# 16encoder.net
KiCad netlist of a schematic drawn in Altium Designer
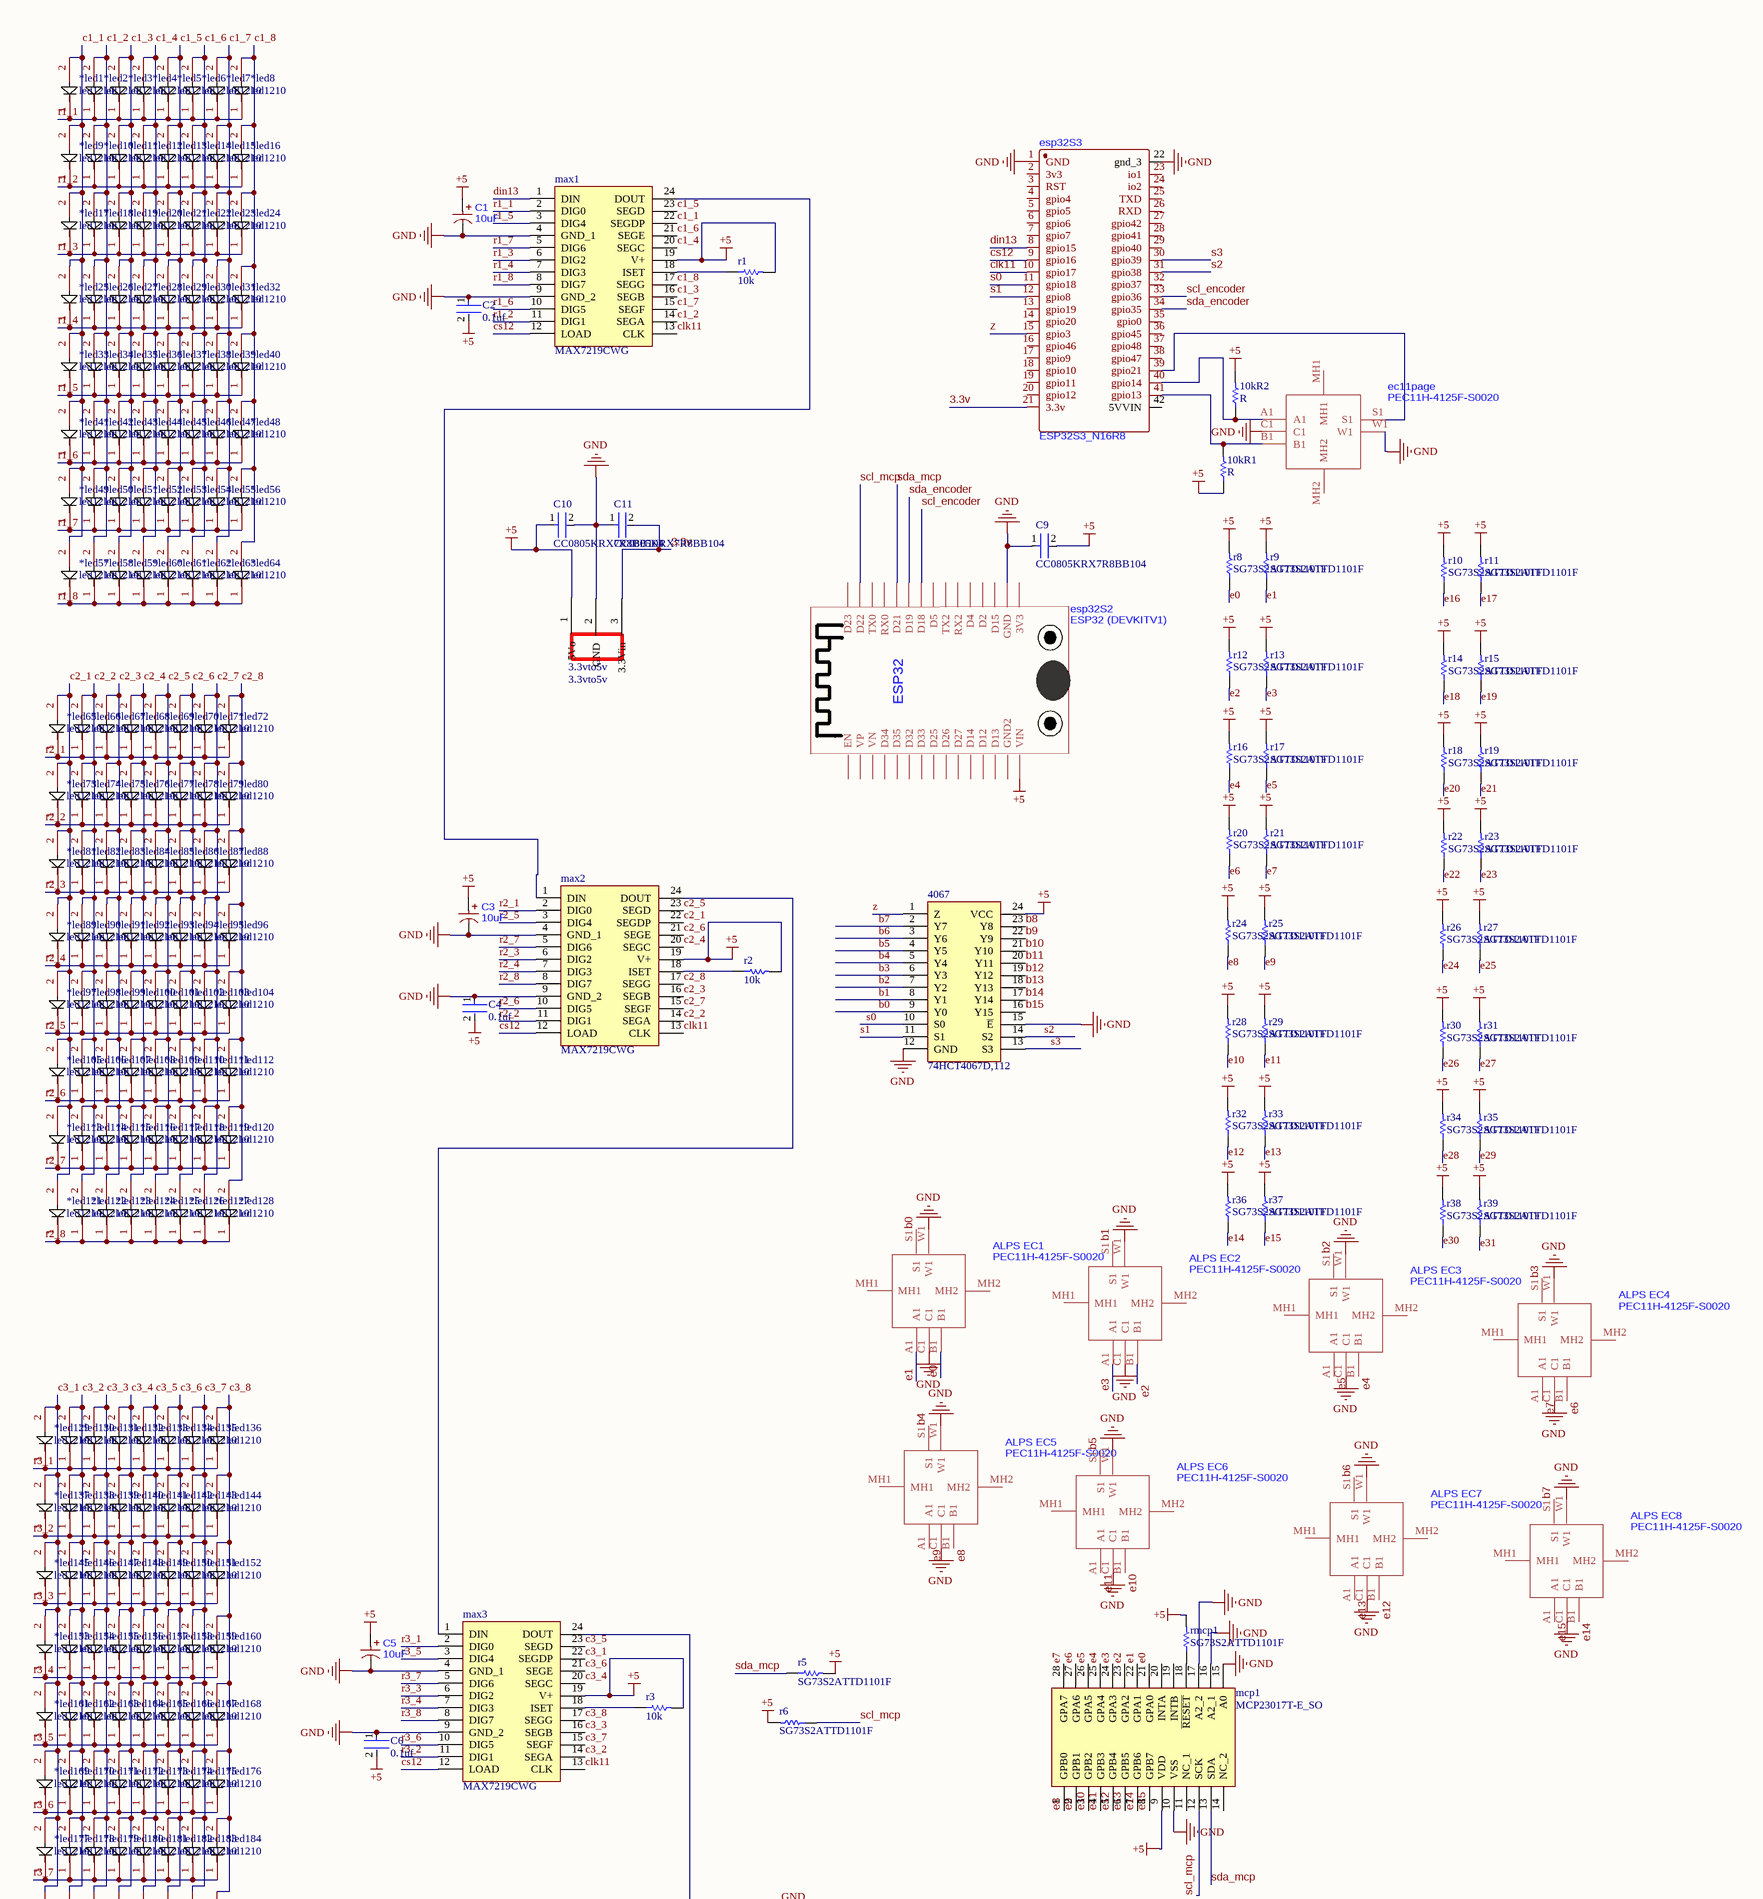
[diagram p0: 16encoder.SchDoc, top]
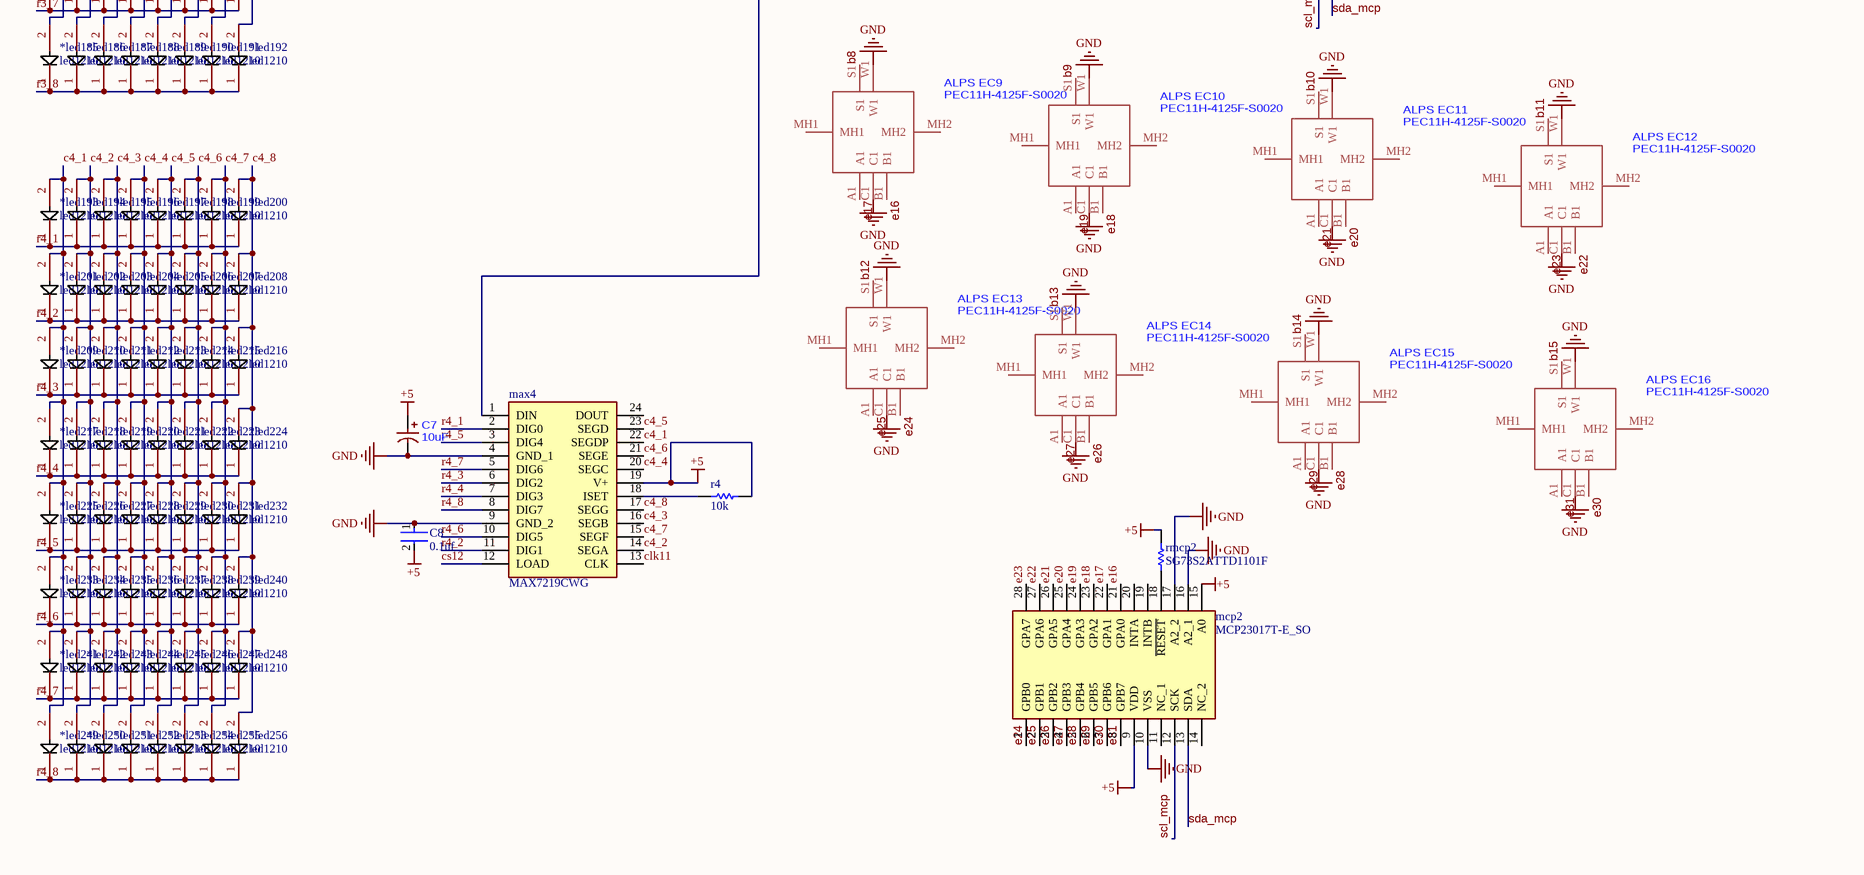
[diagram p1: 16encoder.SchDoc, bottom]

(export (version "E")
  (design (tool "Eeschema 10.0.6"))
  (components
    (comp (ref "*led1") (value "led1210") (footprint "1210贴片led") (libsource (lib "8") (part "led1210")))
    (comp (ref "*led2") (value "led1210") (footprint "1210贴片led") (libsource (lib "8") (part "led1210")))
    (comp (ref "*led3") (value "led1210") (footprint "1210贴片led") (libsource (lib "8") (part "led1210")))
    (comp (ref "*led4") (value "led1210") (footprint "1210贴片led") (libsource (lib "8") (part "led1210")))
    (comp (ref "*led5") (value "led1210") (footprint "1210贴片led") (libsource (lib "8") (part "led1210")))
    (comp (ref "*led6") (value "led1210") (footprint "1210贴片led") (libsource (lib "8") (part "led1210")))
    (comp (ref "*led7") (value "led1210") (footprint "1210贴片led") (libsource (lib "8") (part "led1210")))
    (comp (ref "*led8") (value "led1210") (footprint "1210贴片led") (libsource (lib "8") (part "led1210")))
    (comp (ref "*led9") (value "led1210") (footprint "1210贴片led") (libsource (lib "8") (part "led1210")))
    (comp (ref "*led10") (value "led1210") (footprint "1210贴片led") (libsource (lib "8") (part "led1210")))
    (comp (ref "*led11") (value "led1210") (footprint "1210贴片led") (libsource (lib "8") (part "led1210")))
    (comp (ref "*led12") (value "led1210") (footprint "1210贴片led") (libsource (lib "8") (part "led1210")))
    (comp (ref "*led13") (value "led1210") (footprint "1210贴片led") (libsource (lib "8") (part "led1210")))
    (comp (ref "*led14") (value "led1210") (footprint "1210贴片led") (libsource (lib "8") (part "led1210")))
    (comp (ref "*led15") (value "led1210") (footprint "1210贴片led") (libsource (lib "8") (part "led1210")))
    (comp (ref "*led16") (value "led1210") (footprint "1210贴片led") (libsource (lib "8") (part "led1210")))
    (comp (ref "*led17") (value "led1210") (footprint "1210贴片led") (libsource (lib "8") (part "led1210")))
    (comp (ref "*led18") (value "led1210") (footprint "1210贴片led") (libsource (lib "8") (part "led1210")))
    (comp (ref "*led19") (value "led1210") (footprint "1210贴片led") (libsource (lib "8") (part "led1210")))
    (comp (ref "*led20") (value "led1210") (footprint "1210贴片led") (libsource (lib "8") (part "led1210")))
    (comp (ref "*led21") (value "led1210") (footprint "1210贴片led") (libsource (lib "8") (part "led1210")))
    (comp (ref "*led22") (value "led1210") (footprint "1210贴片led") (libsource (lib "8") (part "led1210")))
    (comp (ref "*led23") (value "led1210") (footprint "1210贴片led") (libsource (lib "8") (part "led1210")))
    (comp (ref "*led24") (value "led1210") (footprint "1210贴片led") (libsource (lib "8") (part "led1210")))
    (comp (ref "*led25") (value "led1210") (footprint "1210贴片led") (libsource (lib "8") (part "led1210")))
    (comp (ref "*led26") (value "led1210") (footprint "1210贴片led") (libsource (lib "8") (part "led1210")))
    (comp (ref "*led27") (value "led1210") (footprint "1210贴片led") (libsource (lib "8") (part "led1210")))
    (comp (ref "*led28") (value "led1210") (footprint "1210贴片led") (libsource (lib "8") (part "led1210")))
    (comp (ref "*led29") (value "led1210") (footprint "1210贴片led") (libsource (lib "8") (part "led1210")))
    (comp (ref "*led30") (value "led1210") (footprint "1210贴片led") (libsource (lib "8") (part "led1210")))
    (comp (ref "*led31") (value "led1210") (footprint "1210贴片led") (libsource (lib "8") (part "led1210")))
    (comp (ref "*led32") (value "led1210") (footprint "1210贴片led") (libsource (lib "8") (part "led1210")))
    (comp (ref "*led33") (value "led1210") (footprint "1210贴片led") (libsource (lib "8") (part "led1210")))
    (comp (ref "*led34") (value "led1210") (footprint "1210贴片led") (libsource (lib "8") (part "led1210")))
    (comp (ref "*led35") (value "led1210") (footprint "1210贴片led") (libsource (lib "8") (part "led1210")))
    (comp (ref "*led36") (value "led1210") (footprint "1210贴片led") (libsource (lib "8") (part "led1210")))
    (comp (ref "*led37") (value "led1210") (footprint "1210贴片led") (libsource (lib "8") (part "led1210")))
    (comp (ref "*led38") (value "led1210") (footprint "1210贴片led") (libsource (lib "8") (part "led1210")))
    (comp (ref "*led39") (value "led1210") (footprint "1210贴片led") (libsource (lib "8") (part "led1210")))
    (comp (ref "*led40") (value "led1210") (footprint "1210贴片led") (libsource (lib "8") (part "led1210")))
    (comp (ref "*led41") (value "led1210") (footprint "1210贴片led") (libsource (lib "8") (part "led1210")))
    (comp (ref "*led42") (value "led1210") (footprint "1210贴片led") (libsource (lib "8") (part "led1210")))
    (comp (ref "*led43") (value "led1210") (footprint "1210贴片led") (libsource (lib "8") (part "led1210")))
    (comp (ref "*led44") (value "led1210") (footprint "1210贴片led") (libsource (lib "8") (part "led1210")))
    (comp (ref "*led45") (value "led1210") (footprint "1210贴片led") (libsource (lib "8") (part "led1210")))
    (comp (ref "*led46") (value "led1210") (footprint "1210贴片led") (libsource (lib "8") (part "led1210")))
    (comp (ref "*led47") (value "led1210") (footprint "1210贴片led") (libsource (lib "8") (part "led1210")))
    (comp (ref "*led48") (value "led1210") (footprint "1210贴片led") (libsource (lib "8") (part "led1210")))
    (comp (ref "*led49") (value "led1210") (footprint "1210贴片led") (libsource (lib "8") (part "led1210")))
    (comp (ref "*led50") (value "led1210") (footprint "1210贴片led") (libsource (lib "8") (part "led1210")))
    (comp (ref "*led51") (value "led1210") (footprint "1210贴片led") (libsource (lib "8") (part "led1210")))
    (comp (ref "*led52") (value "led1210") (footprint "1210贴片led") (libsource (lib "8") (part "led1210")))
    (comp (ref "*led53") (value "led1210") (footprint "1210贴片led") (libsource (lib "8") (part "led1210")))
    (comp (ref "*led54") (value "led1210") (footprint "1210贴片led") (libsource (lib "8") (part "led1210")))
    (comp (ref "*led55") (value "led1210") (footprint "1210贴片led") (libsource (lib "8") (part "led1210")))
    (comp (ref "*led56") (value "led1210") (footprint "1210贴片led") (libsource (lib "8") (part "led1210")))
    (comp (ref "*led57") (value "led1210") (footprint "1210贴片led") (libsource (lib "8") (part "led1210")))
    (comp (ref "*led58") (value "led1210") (footprint "1210贴片led") (libsource (lib "8") (part "led1210")))
    (comp (ref "*led59") (value "led1210") (footprint "1210贴片led") (libsource (lib "8") (part "led1210")))
    (comp (ref "*led60") (value "led1210") (footprint "1210贴片led") (libsource (lib "8") (part "led1210")))
    (comp (ref "*led61") (value "led1210") (footprint "1210贴片led") (libsource (lib "8") (part "led1210")))
    (comp (ref "*led62") (value "led1210") (footprint "1210贴片led") (libsource (lib "8") (part "led1210")))
    (comp (ref "*led63") (value "led1210") (footprint "1210贴片led") (libsource (lib "8") (part "led1210")))
    (comp (ref "*led64") (value "led1210") (footprint "1210贴片led") (libsource (lib "8") (part "led1210")))
    (comp (ref "*led65") (value "led1210") (footprint "1210贴片led") (libsource (lib "8") (part "led1210")))
    (comp (ref "*led66") (value "led1210") (footprint "1210贴片led") (libsource (lib "8") (part "led1210")))
    (comp (ref "*led67") (value "led1210") (footprint "1210贴片led") (libsource (lib "8") (part "led1210")))
    (comp (ref "*led68") (value "led1210") (footprint "1210贴片led") (libsource (lib "8") (part "led1210")))
    (comp (ref "*led69") (value "led1210") (footprint "1210贴片led") (libsource (lib "8") (part "led1210")))
    (comp (ref "*led70") (value "led1210") (footprint "1210贴片led") (libsource (lib "8") (part "led1210")))
    (comp (ref "*led71") (value "led1210") (footprint "1210贴片led") (libsource (lib "8") (part "led1210")))
    (comp (ref "*led72") (value "led1210") (footprint "1210贴片led") (libsource (lib "8") (part "led1210")))
    (comp (ref "*led73") (value "led1210") (footprint "1210贴片led") (libsource (lib "8") (part "led1210")))
    (comp (ref "*led74") (value "led1210") (footprint "1210贴片led") (libsource (lib "8") (part "led1210")))
    (comp (ref "*led75") (value "led1210") (footprint "1210贴片led") (libsource (lib "8") (part "led1210")))
    (comp (ref "*led76") (value "led1210") (footprint "1210贴片led") (libsource (lib "8") (part "led1210")))
    (comp (ref "*led77") (value "led1210") (footprint "1210贴片led") (libsource (lib "8") (part "led1210")))
    (comp (ref "*led78") (value "led1210") (footprint "1210贴片led") (libsource (lib "8") (part "led1210")))
    (comp (ref "*led79") (value "led1210") (footprint "1210贴片led") (libsource (lib "8") (part "led1210")))
    (comp (ref "*led80") (value "led1210") (footprint "1210贴片led") (libsource (lib "8") (part "led1210")))
    (comp (ref "*led81") (value "led1210") (footprint "1210贴片led") (libsource (lib "8") (part "led1210")))
    (comp (ref "*led82") (value "led1210") (footprint "1210贴片led") (libsource (lib "8") (part "led1210")))
    (comp (ref "*led83") (value "led1210") (footprint "1210贴片led") (libsource (lib "8") (part "led1210")))
    (comp (ref "*led84") (value "led1210") (footprint "1210贴片led") (libsource (lib "8") (part "led1210")))
    (comp (ref "*led85") (value "led1210") (footprint "1210贴片led") (libsource (lib "8") (part "led1210")))
    (comp (ref "*led86") (value "led1210") (footprint "1210贴片led") (libsource (lib "8") (part "led1210")))
    (comp (ref "*led87") (value "led1210") (footprint "1210贴片led") (libsource (lib "8") (part "led1210")))
    (comp (ref "*led88") (value "led1210") (footprint "1210贴片led") (libsource (lib "8") (part "led1210")))
    (comp (ref "*led89") (value "led1210") (footprint "1210贴片led") (libsource (lib "8") (part "led1210")))
    (comp (ref "*led90") (value "led1210") (footprint "1210贴片led") (libsource (lib "8") (part "led1210")))
    (comp (ref "*led91") (value "led1210") (footprint "1210贴片led") (libsource (lib "8") (part "led1210")))
    (comp (ref "*led92") (value "led1210") (footprint "1210贴片led") (libsource (lib "8") (part "led1210")))
    (comp (ref "*led93") (value "led1210") (footprint "1210贴片led") (libsource (lib "8") (part "led1210")))
    (comp (ref "*led94") (value "led1210") (footprint "1210贴片led") (libsource (lib "8") (part "led1210")))
    (comp (ref "*led95") (value "led1210") (footprint "1210贴片led") (libsource (lib "8") (part "led1210")))
    (comp (ref "*led96") (value "led1210") (footprint "1210贴片led") (libsource (lib "8") (part "led1210")))
    (comp (ref "*led97") (value "led1210") (footprint "1210贴片led") (libsource (lib "8") (part "led1210")))
    (comp (ref "*led98") (value "led1210") (footprint "1210贴片led") (libsource (lib "8") (part "led1210")))
    (comp (ref "*led99") (value "led1210") (footprint "1210贴片led") (libsource (lib "8") (part "led1210")))
    (comp (ref "*led100") (value "led1210") (footprint "1210贴片led") (libsource (lib "8") (part "led1210")))
    (comp (ref "*led101") (value "led1210") (footprint "1210贴片led") (libsource (lib "8") (part "led1210")))
    (comp (ref "*led102") (value "led1210") (footprint "1210贴片led") (libsource (lib "8") (part "led1210")))
    (comp (ref "*led103") (value "led1210") (footprint "1210贴片led") (libsource (lib "8") (part "led1210")))
    (comp (ref "*led104") (value "led1210") (footprint "1210贴片led") (libsource (lib "8") (part "led1210")))
    (comp (ref "*led105") (value "led1210") (footprint "1210贴片led") (libsource (lib "8") (part "led1210")))
    (comp (ref "*led106") (value "led1210") (footprint "1210贴片led") (libsource (lib "8") (part "led1210")))
    (comp (ref "*led107") (value "led1210") (footprint "1210贴片led") (libsource (lib "8") (part "led1210")))
    (comp (ref "*led108") (value "led1210") (footprint "1210贴片led") (libsource (lib "8") (part "led1210")))
    (comp (ref "*led109") (value "led1210") (footprint "1210贴片led") (libsource (lib "8") (part "led1210")))
    (comp (ref "*led110") (value "led1210") (footprint "1210贴片led") (libsource (lib "8") (part "led1210")))
    (comp (ref "*led111") (value "led1210") (footprint "1210贴片led") (libsource (lib "8") (part "led1210")))
    (comp (ref "*led112") (value "led1210") (footprint "1210贴片led") (libsource (lib "8") (part "led1210")))
    (comp (ref "*led113") (value "led1210") (footprint "1210贴片led") (libsource (lib "8") (part "led1210")))
    (comp (ref "*led114") (value "led1210") (footprint "1210贴片led") (libsource (lib "8") (part "led1210")))
    (comp (ref "*led115") (value "led1210") (footprint "1210贴片led") (libsource (lib "8") (part "led1210")))
    (comp (ref "*led116") (value "led1210") (footprint "1210贴片led") (libsource (lib "8") (part "led1210")))
    (comp (ref "*led117") (value "led1210") (footprint "1210贴片led") (libsource (lib "8") (part "led1210")))
    (comp (ref "*led118") (value "led1210") (footprint "1210贴片led") (libsource (lib "8") (part "led1210")))
    (comp (ref "*led119") (value "led1210") (footprint "1210贴片led") (libsource (lib "8") (part "led1210")))
    (comp (ref "*led120") (value "led1210") (footprint "1210贴片led") (libsource (lib "8") (part "led1210")))
    (comp (ref "*led121") (value "led1210") (footprint "1210贴片led") (libsource (lib "8") (part "led1210")))
    (comp (ref "*led122") (value "led1210") (footprint "1210贴片led") (libsource (lib "8") (part "led1210")))
    (comp (ref "*led123") (value "led1210") (footprint "1210贴片led") (libsource (lib "8") (part "led1210")))
    (comp (ref "*led124") (value "led1210") (footprint "1210贴片led") (libsource (lib "8") (part "led1210")))
    (comp (ref "*led125") (value "led1210") (footprint "1210贴片led") (libsource (lib "8") (part "led1210")))
    (comp (ref "*led126") (value "led1210") (footprint "1210贴片led") (libsource (lib "8") (part "led1210")))
    (comp (ref "*led127") (value "led1210") (footprint "1210贴片led") (libsource (lib "8") (part "led1210")))
    (comp (ref "*led128") (value "led1210") (footprint "1210贴片led") (libsource (lib "8") (part "led1210")))
    (comp (ref "*led129") (value "led1210") (footprint "1210贴片led") (libsource (lib "8") (part "led1210")))
    (comp (ref "*led130") (value "led1210") (footprint "1210贴片led") (libsource (lib "8") (part "led1210")))
    (comp (ref "*led131") (value "led1210") (footprint "1210贴片led") (libsource (lib "8") (part "led1210")))
    (comp (ref "*led132") (value "led1210") (footprint "1210贴片led") (libsource (lib "8") (part "led1210")))
    (comp (ref "*led133") (value "led1210") (footprint "1210贴片led") (libsource (lib "8") (part "led1210")))
    (comp (ref "*led134") (value "led1210") (footprint "1210贴片led") (libsource (lib "8") (part "led1210")))
    (comp (ref "*led135") (value "led1210") (footprint "1210贴片led") (libsource (lib "8") (part "led1210")))
    (comp (ref "*led136") (value "led1210") (footprint "1210贴片led") (libsource (lib "8") (part "led1210")))
    (comp (ref "*led137") (value "led1210") (footprint "1210贴片led") (libsource (lib "8") (part "led1210")))
    (comp (ref "*led138") (value "led1210") (footprint "1210贴片led") (libsource (lib "8") (part "led1210")))
    (comp (ref "*led139") (value "led1210") (footprint "1210贴片led") (libsource (lib "8") (part "led1210")))
    (comp (ref "*led140") (value "led1210") (footprint "1210贴片led") (libsource (lib "8") (part "led1210")))
    (comp (ref "*led141") (value "led1210") (footprint "1210贴片led") (libsource (lib "8") (part "led1210")))
    (comp (ref "*led142") (value "led1210") (footprint "1210贴片led") (libsource (lib "8") (part "led1210")))
    (comp (ref "*led143") (value "led1210") (footprint "1210贴片led") (libsource (lib "8") (part "led1210")))
    (comp (ref "*led144") (value "led1210") (footprint "1210贴片led") (libsource (lib "8") (part "led1210")))
    (comp (ref "*led145") (value "led1210") (footprint "1210贴片led") (libsource (lib "8") (part "led1210")))
    (comp (ref "*led146") (value "led1210") (footprint "1210贴片led") (libsource (lib "8") (part "led1210")))
    (comp (ref "*led147") (value "led1210") (footprint "1210贴片led") (libsource (lib "8") (part "led1210")))
    (comp (ref "*led148") (value "led1210") (footprint "1210贴片led") (libsource (lib "8") (part "led1210")))
    (comp (ref "*led149") (value "led1210") (footprint "1210贴片led") (libsource (lib "8") (part "led1210")))
    (comp (ref "*led150") (value "led1210") (footprint "1210贴片led") (libsource (lib "8") (part "led1210")))
    (comp (ref "*led151") (value "led1210") (footprint "1210贴片led") (libsource (lib "8") (part "led1210")))
    (comp (ref "*led152") (value "led1210") (footprint "1210贴片led") (libsource (lib "8") (part "led1210")))
    (comp (ref "*led153") (value "led1210") (footprint "1210贴片led") (libsource (lib "8") (part "led1210")))
    (comp (ref "*led154") (value "led1210") (footprint "1210贴片led") (libsource (lib "8") (part "led1210")))
    (comp (ref "*led155") (value "led1210") (footprint "1210贴片led") (libsource (lib "8") (part "led1210")))
    (comp (ref "*led156") (value "led1210") (footprint "1210贴片led") (libsource (lib "8") (part "led1210")))
    (comp (ref "*led157") (value "led1210") (footprint "1210贴片led") (libsource (lib "8") (part "led1210")))
    (comp (ref "*led158") (value "led1210") (footprint "1210贴片led") (libsource (lib "8") (part "led1210")))
    (comp (ref "*led159") (value "led1210") (footprint "1210贴片led") (libsource (lib "8") (part "led1210")))
    (comp (ref "*led160") (value "led1210") (footprint "1210贴片led") (libsource (lib "8") (part "led1210")))
    (comp (ref "*led161") (value "led1210") (footprint "1210贴片led") (libsource (lib "8") (part "led1210")))
    (comp (ref "*led162") (value "led1210") (footprint "1210贴片led") (libsource (lib "8") (part "led1210")))
    (comp (ref "*led163") (value "led1210") (footprint "1210贴片led") (libsource (lib "8") (part "led1210")))
    (comp (ref "*led164") (value "led1210") (footprint "1210贴片led") (libsource (lib "8") (part "led1210")))
    (comp (ref "*led165") (value "led1210") (footprint "1210贴片led") (libsource (lib "8") (part "led1210")))
    (comp (ref "*led166") (value "led1210") (footprint "1210贴片led") (libsource (lib "8") (part "led1210")))
    (comp (ref "*led167") (value "led1210") (footprint "1210贴片led") (libsource (lib "8") (part "led1210")))
    (comp (ref "*led168") (value "led1210") (footprint "1210贴片led") (libsource (lib "8") (part "led1210")))
    (comp (ref "*led169") (value "led1210") (footprint "1210贴片led") (libsource (lib "8") (part "led1210")))
    (comp (ref "*led170") (value "led1210") (footprint "1210贴片led") (libsource (lib "8") (part "led1210")))
    (comp (ref "*led171") (value "led1210") (footprint "1210贴片led") (libsource (lib "8") (part "led1210")))
    (comp (ref "*led172") (value "led1210") (footprint "1210贴片led") (libsource (lib "8") (part "led1210")))
    (comp (ref "*led173") (value "led1210") (footprint "1210贴片led") (libsource (lib "8") (part "led1210")))
    (comp (ref "*led174") (value "led1210") (footprint "1210贴片led") (libsource (lib "8") (part "led1210")))
    (comp (ref "*led175") (value "led1210") (footprint "1210贴片led") (libsource (lib "8") (part "led1210")))
    (comp (ref "*led176") (value "led1210") (footprint "1210贴片led") (libsource (lib "8") (part "led1210")))
    (comp (ref "*led177") (value "led1210") (footprint "1210贴片led") (libsource (lib "8") (part "led1210")))
    (comp (ref "*led178") (value "led1210") (footprint "1210贴片led") (libsource (lib "8") (part "led1210")))
    (comp (ref "*led179") (value "led1210") (footprint "1210贴片led") (libsource (lib "8") (part "led1210")))
    (comp (ref "*led180") (value "led1210") (footprint "1210贴片led") (libsource (lib "8") (part "led1210")))
    (comp (ref "*led181") (value "led1210") (footprint "1210贴片led") (libsource (lib "8") (part "led1210")))
    (comp (ref "*led182") (value "led1210") (footprint "1210贴片led") (libsource (lib "8") (part "led1210")))
    (comp (ref "*led183") (value "led1210") (footprint "1210贴片led") (libsource (lib "8") (part "led1210")))
    (comp (ref "*led184") (value "led1210") (footprint "1210贴片led") (libsource (lib "8") (part "led1210")))
    (comp (ref "*led185") (value "led1210") (footprint "1210贴片led") (libsource (lib "8") (part "led1210")))
    (comp (ref "*led186") (value "led1210") (footprint "1210贴片led") (libsource (lib "8") (part "led1210")))
    (comp (ref "*led187") (value "led1210") (footprint "1210贴片led") (libsource (lib "8") (part "led1210")))
    (comp (ref "*led188") (value "led1210") (footprint "1210贴片led") (libsource (lib "8") (part "led1210")))
    (comp (ref "*led189") (value "led1210") (footprint "1210贴片led") (libsource (lib "8") (part "led1210")))
    (comp (ref "*led190") (value "led1210") (footprint "1210贴片led") (libsource (lib "8") (part "led1210")))
    (comp (ref "*led191") (value "led1210") (footprint "1210贴片led") (libsource (lib "8") (part "led1210")))
    (comp (ref "*led192") (value "led1210") (footprint "1210贴片led") (libsource (lib "8") (part "led1210")))
    (comp (ref "*led193") (value "led1210") (footprint "1210贴片led") (libsource (lib "8") (part "led1210")))
    (comp (ref "*led194") (value "led1210") (footprint "1210贴片led") (libsource (lib "8") (part "led1210")))
    (comp (ref "*led195") (value "led1210") (footprint "1210贴片led") (libsource (lib "8") (part "led1210")))
    (comp (ref "*led196") (value "led1210") (footprint "1210贴片led") (libsource (lib "8") (part "led1210")))
    (comp (ref "*led197") (value "led1210") (footprint "1210贴片led") (libsource (lib "8") (part "led1210")))
    (comp (ref "*led198") (value "led1210") (footprint "1210贴片led") (libsource (lib "8") (part "led1210")))
    (comp (ref "*led199") (value "led1210") (footprint "1210贴片led") (libsource (lib "8") (part "led1210")))
    (comp (ref "*led200") (value "led1210") (footprint "1210贴片led") (libsource (lib "8") (part "led1210")))
    (comp (ref "*led201") (value "led1210") (footprint "1210贴片led") (libsource (lib "8") (part "led1210")))
    (comp (ref "*led202") (value "led1210") (footprint "1210贴片led") (libsource (lib "8") (part "led1210")))
    (comp (ref "*led203") (value "led1210") (footprint "1210贴片led") (libsource (lib "8") (part "led1210")))
    (comp (ref "*led204") (value "led1210") (footprint "1210贴片led") (libsource (lib "8") (part "led1210")))
    (comp (ref "*led205") (value "led1210") (footprint "1210贴片led") (libsource (lib "8") (part "led1210")))
    (comp (ref "*led206") (value "led1210") (footprint "1210贴片led") (libsource (lib "8") (part "led1210")))
    (comp (ref "*led207") (value "led1210") (footprint "1210贴片led") (libsource (lib "8") (part "led1210")))
    (comp (ref "*led208") (value "led1210") (footprint "1210贴片led") (libsource (lib "8") (part "led1210")))
    (comp (ref "*led209") (value "led1210") (footprint "1210贴片led") (libsource (lib "8") (part "led1210")))
    (comp (ref "*led210") (value "led1210") (footprint "1210贴片led") (libsource (lib "8") (part "led1210")))
    (comp (ref "*led211") (value "led1210") (footprint "1210贴片led") (libsource (lib "8") (part "led1210")))
    (comp (ref "*led212") (value "led1210") (footprint "1210贴片led") (libsource (lib "8") (part "led1210")))
    (comp (ref "*led213") (value "led1210") (footprint "1210贴片led") (libsource (lib "8") (part "led1210")))
    (comp (ref "*led214") (value "led1210") (footprint "1210贴片led") (libsource (lib "8") (part "led1210")))
    (comp (ref "*led215") (value "led1210") (footprint "1210贴片led") (libsource (lib "8") (part "led1210")))
    (comp (ref "*led216") (value "led1210") (footprint "1210贴片led") (libsource (lib "8") (part "led1210")))
    (comp (ref "*led217") (value "led1210") (footprint "1210贴片led") (libsource (lib "8") (part "led1210")))
    (comp (ref "*led218") (value "led1210") (footprint "1210贴片led") (libsource (lib "8") (part "led1210")))
    (comp (ref "*led219") (value "led1210") (footprint "1210贴片led") (libsource (lib "8") (part "led1210")))
    (comp (ref "*led220") (value "led1210") (footprint "1210贴片led") (libsource (lib "8") (part "led1210")))
    (comp (ref "*led221") (value "led1210") (footprint "1210贴片led") (libsource (lib "8") (part "led1210")))
    (comp (ref "*led222") (value "led1210") (footprint "1210贴片led") (libsource (lib "8") (part "led1210")))
    (comp (ref "*led223") (value "led1210") (footprint "1210贴片led") (libsource (lib "8") (part "led1210")))
    (comp (ref "*led224") (value "led1210") (footprint "1210贴片led") (libsource (lib "8") (part "led1210")))
    (comp (ref "*led225") (value "led1210") (footprint "1210贴片led") (libsource (lib "8") (part "led1210")))
    (comp (ref "*led226") (value "led1210") (footprint "1210贴片led") (libsource (lib "8") (part "led1210")))
    (comp (ref "*led227") (value "led1210") (footprint "1210贴片led") (libsource (lib "8") (part "led1210")))
    (comp (ref "*led228") (value "led1210") (footprint "1210贴片led") (libsource (lib "8") (part "led1210")))
    (comp (ref "*led229") (value "led1210") (footprint "1210贴片led") (libsource (lib "8") (part "led1210")))
    (comp (ref "*led230") (value "led1210") (footprint "1210贴片led") (libsource (lib "8") (part "led1210")))
    (comp (ref "*led231") (value "led1210") (footprint "1210贴片led") (libsource (lib "8") (part "led1210")))
    (comp (ref "*led232") (value "led1210") (footprint "1210贴片led") (libsource (lib "8") (part "led1210")))
    (comp (ref "*led233") (value "led1210") (footprint "1210贴片led") (libsource (lib "8") (part "led1210")))
    (comp (ref "*led234") (value "led1210") (footprint "1210贴片led") (libsource (lib "8") (part "led1210")))
    (comp (ref "*led235") (value "led1210") (footprint "1210贴片led") (libsource (lib "8") (part "led1210")))
    (comp (ref "*led236") (value "led1210") (footprint "1210贴片led") (libsource (lib "8") (part "led1210")))
    (comp (ref "*led237") (value "led1210") (footprint "1210贴片led") (libsource (lib "8") (part "led1210")))
    (comp (ref "*led238") (value "led1210") (footprint "1210贴片led") (libsource (lib "8") (part "led1210")))
    (comp (ref "*led239") (value "led1210") (footprint "1210贴片led") (libsource (lib "8") (part "led1210")))
    (comp (ref "*led240") (value "led1210") (footprint "1210贴片led") (libsource (lib "8") (part "led1210")))
    (comp (ref "*led241") (value "led1210") (footprint "1210贴片led") (libsource (lib "8") (part "led1210")))
    (comp (ref "*led242") (value "led1210") (footprint "1210贴片led") (libsource (lib "8") (part "led1210")))
    (comp (ref "*led243") (value "led1210") (footprint "1210贴片led") (libsource (lib "8") (part "led1210")))
    (comp (ref "*led244") (value "led1210") (footprint "1210贴片led") (libsource (lib "8") (part "led1210")))
    (comp (ref "*led245") (value "led1210") (footprint "1210贴片led") (libsource (lib "8") (part "led1210")))
    (comp (ref "*led246") (value "led1210") (footprint "1210贴片led") (libsource (lib "8") (part "led1210")))
    (comp (ref "*led247") (value "led1210") (footprint "1210贴片led") (libsource (lib "8") (part "led1210")))
    (comp (ref "*led248") (value "led1210") (footprint "1210贴片led") (libsource (lib "8") (part "led1210")))
    (comp (ref "*led249") (value "led1210") (footprint "1210贴片led") (libsource (lib "8") (part "led1210")))
    (comp (ref "*led250") (value "led1210") (footprint "1210贴片led") (libsource (lib "8") (part "led1210")))
    (comp (ref "*led251") (value "led1210") (footprint "1210贴片led") (libsource (lib "8") (part "led1210")))
    (comp (ref "*led252") (value "led1210") (footprint "1210贴片led") (libsource (lib "8") (part "led1210")))
    (comp (ref "*led253") (value "led1210") (footprint "1210贴片led") (libsource (lib "8") (part "led1210")))
    (comp (ref "*led254") (value "led1210") (footprint "1210贴片led") (libsource (lib "8") (part "led1210")))
    (comp (ref "*led255") (value "led1210") (footprint "1210贴片led") (libsource (lib "8") (part "led1210")))
    (comp (ref "*led256") (value "led1210") (footprint "1210贴片led") (libsource (lib "8") (part "led1210")))
    (comp (ref "3.3vto5v")
      (value "3.3vto5v")
      (footprint "3.3vto5v")
      (libsource (lib "8_1") (part "3.3vto5v"))
    )
    (comp (ref "10kR1")
      (value "R")
      (footprint "RESC2013X60X30LL20T20")
      (fields (field (name "MANUFACTURER") "KOA Speer") (field (name "PART NUMBER") "SG73S2ATTD1101F"))
      (libsource (lib "8_1") (part "CMP-2001-02660-1"))
    )
    (comp (ref "10kR2")
      (value "R")
      (footprint "RESC2013X60X30LL20T20")
      (fields (field (name "MANUFACTURER") "KOA Speer") (field (name "PART NUMBER") "SG73S2ATTD1101F"))
      (libsource (lib "8_1") (part "CMP-2001-02660-1"))
    )
    (comp (ref "4067")
      (value "74HCT4067D,112")
      (footprint "SamacSys:SOIC127P1032X265-24N")
      (description "Integrated Circuit")
      (fields (field (name "MOUSER PART NUMBER") "771-74HCT4067D"))
      (libsource (lib "*") (part "74HCT4067D,112"))
    )
    (comp (ref "ALPS EC1")
      (value "PEC11H-4125F-S0020")
      (footprint "ALPS EC11")
      (libsource (lib "midi_sub") (part "PEC11H-4125F-S0020"))
    )
    (comp (ref "ALPS EC2")
      (value "PEC11H-4125F-S0020")
      (footprint "ALPS EC11")
      (libsource (lib "midi_sub") (part "PEC11H-4125F-S0020"))
    )
    (comp (ref "ALPS EC3")
      (value "PEC11H-4125F-S0020")
      (footprint "ALPS EC11")
      (libsource (lib "midi_sub") (part "PEC11H-4125F-S0020"))
    )
    (comp (ref "ALPS EC4")
      (value "PEC11H-4125F-S0020")
      (footprint "ALPS EC11")
      (libsource (lib "midi_sub") (part "PEC11H-4125F-S0020"))
    )
    (comp (ref "ALPS EC5")
      (value "PEC11H-4125F-S0020")
      (footprint "ALPS EC11")
      (libsource (lib "midi_sub") (part "PEC11H-4125F-S0020"))
    )
    (comp (ref "ALPS EC6")
      (value "PEC11H-4125F-S0020")
      (footprint "ALPS EC11")
      (libsource (lib "midi_sub") (part "PEC11H-4125F-S0020"))
    )
    (comp (ref "ALPS EC7")
      (value "PEC11H-4125F-S0020")
      (footprint "ALPS EC11")
      (libsource (lib "midi_sub") (part "PEC11H-4125F-S0020"))
    )
    (comp (ref "ALPS EC8")
      (value "PEC11H-4125F-S0020")
      (footprint "ALPS EC11")
      (libsource (lib "midi_sub") (part "PEC11H-4125F-S0020"))
    )
    (comp (ref "ALPS EC9")
      (value "PEC11H-4125F-S0020")
      (footprint "ALPS EC11")
      (libsource (lib "midi_sub") (part "PEC11H-4125F-S0020"))
    )
    (comp (ref "ALPS EC10")
      (value "PEC11H-4125F-S0020")
      (footprint "ALPS EC11")
      (libsource (lib "midi_sub") (part "PEC11H-4125F-S0020"))
    )
    (comp (ref "ALPS EC11")
      (value "PEC11H-4125F-S0020")
      (footprint "ALPS EC11")
      (libsource (lib "midi_sub") (part "PEC11H-4125F-S0020"))
    )
    (comp (ref "ALPS EC12")
      (value "PEC11H-4125F-S0020")
      (footprint "ALPS EC11")
      (libsource (lib "midi_sub") (part "PEC11H-4125F-S0020"))
    )
    (comp (ref "ALPS EC13")
      (value "PEC11H-4125F-S0020")
      (footprint "ALPS EC11")
      (libsource (lib "midi_sub") (part "PEC11H-4125F-S0020"))
    )
    (comp (ref "ALPS EC14")
      (value "PEC11H-4125F-S0020")
      (footprint "ALPS EC11")
      (libsource (lib "midi_sub") (part "PEC11H-4125F-S0020"))
    )
    (comp (ref "ALPS EC15")
      (value "PEC11H-4125F-S0020")
      (footprint "ALPS EC11")
      (libsource (lib "midi_sub") (part "PEC11H-4125F-S0020"))
    )
    (comp (ref "ALPS EC16")
      (value "PEC11H-4125F-S0020")
      (footprint "ALPS EC11")
      (libsource (lib "midi_sub") (part "PEC11H-4125F-S0020"))
    )
    (comp (ref "C1")
      (value "10uF")
      (footprint "ELECTROLYTIC CAPACITOR SMD 4X5.4")
      (libsource (lib "sub_1") (part "4.3 X 4.3 ELECTROLYTIC  CAPACITOR SMD μF"))
    )
    (comp (ref "C2")
      (value "0.1uf")
      (footprint "FP-CC0805-0_85-IPC_A")
      (description "CAP CER 0.1UF 25V X7R 0805")
      (fields (field (name "MANUFACTURER PART NUMBER") "CC0805KRX7R8BB104") (field (name "TOLERANCE") "0.1"))
      (libsource (lib "sub_1") (part "CMP-1036-04410-2"))
    )
    (comp (ref "C3")
      (value "10uF")
      (footprint "ELECTROLYTIC CAPACITOR SMD 4X5.4")
      (libsource (lib "sub_1") (part "4.3 X 4.3 ELECTROLYTIC  CAPACITOR SMD μF"))
    )
    (comp (ref "C4")
      (value "0.1uf")
      (footprint "FP-CC0805-0_85-IPC_A")
      (description "CAP CER 0.1UF 25V X7R 0805")
      (fields (field (name "MANUFACTURER PART NUMBER") "CC0805KRX7R8BB104") (field (name "TOLERANCE") "0.1"))
      (libsource (lib "sub_1") (part "CMP-1036-04410-2"))
    )
    (comp (ref "C5")
      (value "10uF")
      (footprint "ELECTROLYTIC CAPACITOR SMD 4X5.4")
      (libsource (lib "sub_1") (part "4.3 X 4.3 ELECTROLYTIC  CAPACITOR SMD μF"))
    )
    (comp (ref "C6")
      (value "0.1uf")
      (footprint "FP-CC0805-0_85-IPC_A")
      (description "CAP CER 0.1UF 25V X7R 0805")
      (fields (field (name "MANUFACTURER PART NUMBER") "CC0805KRX7R8BB104") (field (name "TOLERANCE") "0.1"))
      (libsource (lib "sub_1") (part "CMP-1036-04410-2"))
    )
    (comp (ref "C7")
      (value "10uF")
      (footprint "ELECTROLYTIC CAPACITOR SMD 4X5.4")
      (libsource (lib "sub_1") (part "4.3 X 4.3 ELECTROLYTIC  CAPACITOR SMD μF"))
    )
    (comp (ref "C8")
      (value "0.1uf")
      (footprint "FP-CC0805-0_85-IPC_A")
      (description "CAP CER 0.1UF 25V X7R 0805")
      (fields (field (name "MANUFACTURER PART NUMBER") "CC0805KRX7R8BB104") (field (name "TOLERANCE") "0.1"))
      (libsource (lib "sub_1") (part "CMP-1036-04410-2"))
    )
    (comp (ref "C9")
      (value "CC0805KRX7R8BB104")
      (footprint "FP-CC0805-0_85-IPC_A")
      (description "CAP CER 0.1UF 25V X7R 0805")
      (fields (field (name "TOLERANCE") "0.1") (field (name "MANUFACTURER") "Yageo"))
      (libsource (lib "midi_sub") (part "CMP-1036-04410-2"))
    )
    (comp (ref "C10")
      (value "CC0805KRX7R8BB104")
      (footprint "FP-CC0805-0_85-IPC_A")
      (description "CAP CER 0.1UF 25V X7R 0805")
      (fields (field (name "TOLERANCE") "0.1") (field (name "MANUFACTURER") "Yageo"))
      (libsource (lib "midi_sub") (part "CMP-1036-04410-2"))
    )
    (comp (ref "C11")
      (value "CC0805KRX7R8BB104")
      (footprint "FP-CC0805-0_85-IPC_A")
      (description "CAP CER 0.1UF 25V X7R 0805")
      (fields (field (name "TOLERANCE") "0.1") (field (name "MANUFACTURER") "Yageo"))
      (libsource (lib "midi_sub") (part "CMP-1036-04410-2"))
    )
    (comp (ref "ec11page")
      (value "PEC11H-4125F-S0020")
      (footprint "ALPS EC11")
      (libsource (lib "midi_sub") (part "PEC11H-4125F-S0020"))
    )
    (comp (ref "esp32S2")
      (value "ESP32 (DEVKITV1)")
      (footprint "ESP32-DEVKITV1_ESP32-DEVKITV1")
      (libsource (lib "8_1") (part "ESP32 (DEVKITV1)"))
    )
    (comp (ref "esp32S3")
      (value "ESP32S3_N16R8")
      (footprint "ESP32 S3 N16R8")
      (libsource (lib "8_1") (part "ESP32S3_N16R8"))
    )
    (comp (ref "max1")
      (value "MAX7219CWG")
      (footprint "SamacSys:SOIC127P1032X265-24N")
      (description "Integrated Circuit")
      (fields (field (name "MOUSER PART NUMBER") "700-MAX7219CWG-NR"))
      (libsource (lib "*") (part "MAX7219CWG"))
    )
    (comp (ref "max2")
      (value "MAX7219CWG")
      (footprint "SamacSys:SOIC127P1032X265-24N")
      (description "Integrated Circuit")
      (fields (field (name "MOUSER PART NUMBER") "700-MAX7219CWG-NR"))
      (libsource (lib "*") (part "MAX7219CWG"))
    )
    (comp (ref "max3")
      (value "MAX7219CWG")
      (footprint "SamacSys:SOIC127P1032X265-24N")
      (description "Integrated Circuit")
      (fields (field (name "MOUSER PART NUMBER") "700-MAX7219CWG-NR"))
      (libsource (lib "*") (part "MAX7219CWG"))
    )
    (comp (ref "max4")
      (value "MAX7219CWG")
      (footprint "SamacSys:SOIC127P1032X265-24N")
      (description "Integrated Circuit")
      (fields (field (name "MOUSER PART NUMBER") "700-MAX7219CWG-NR"))
      (libsource (lib "*") (part "MAX7219CWG"))
    )
    (comp (ref "mcp1")
      (value "MCP23017T-E_SO")
      (footprint "SOIC127P1030X265-28N")
      (description "Integrated Circuit")
      (fields
        (field (name "MANUFACTURER_PART_NUMBER") "MCP23017T-E/SO")
        (field (name "MOUSER PART NUMBER") "579-MCP23017T-E/SO")
      )
      (libsource (lib "sub_1") (part "MCP23017T-E_SO"))
    )
    (comp (ref "mcp2")
      (value "MCP23017T-E_SO")
      (footprint "SOIC127P1030X265-28N")
      (description "Integrated Circuit")
      (fields
        (field (name "MANUFACTURER_PART_NUMBER") "MCP23017T-E/SO")
        (field (name "MOUSER PART NUMBER") "579-MCP23017T-E/SO")
      )
      (libsource (lib "sub_1") (part "MCP23017T-E_SO"))
    )
    (comp (ref "r1")
      (value "10k")
      (footprint "RESC2013X60X30LL20T20")
      (fields (field (name "MANUFACTURER") "KOA Speer") (field (name "PART NUMBER") "SG73S2ATTD1101F"))
      (libsource (lib "sub_1") (part "CMP-2001-02660-1"))
    )
    (comp (ref "r2")
      (value "10k")
      (footprint "RESC2013X60X30LL20T20")
      (fields (field (name "MANUFACTURER") "KOA Speer") (field (name "PART NUMBER") "SG73S2ATTD1101F"))
      (libsource (lib "sub_1") (part "CMP-2001-02660-1"))
    )
    (comp (ref "r3")
      (value "10k")
      (footprint "RESC2013X60X30LL20T20")
      (fields (field (name "MANUFACTURER") "KOA Speer") (field (name "PART NUMBER") "SG73S2ATTD1101F"))
      (libsource (lib "sub_1") (part "CMP-2001-02660-1"))
    )
    (comp (ref "r4")
      (value "10k")
      (footprint "RESC2013X60X30LL20T20")
      (fields (field (name "MANUFACTURER") "KOA Speer") (field (name "PART NUMBER") "SG73S2ATTD1101F"))
      (libsource (lib "sub_1") (part "CMP-2001-02660-1"))
    )
    (comp (ref "r5")
      (value "SG73S2ATTD1101F")
      (footprint "RESC2013X60X30LL20T20")
      (fields (field (name "MANUFACTURER") "KOA Speer"))
      (libsource (lib "sub_1") (part "CMP-2001-02660-1"))
    )
    (comp (ref "r6")
      (value "SG73S2ATTD1101F")
      (footprint "RESC2013X60X30LL20T20")
      (fields (field (name "MANUFACTURER") "KOA Speer"))
      (libsource (lib "sub_1") (part "CMP-2001-02660-1"))
    )
    (comp (ref "r8")
      (value "SG73S2ATTD1101F")
      (footprint "RESC2013X60X30LL20T20")
      (fields (field (name "MANUFACTURER") "KOA Speer"))
      (libsource (lib "sub_1") (part "CMP-2001-02660-1"))
    )
    (comp (ref "r9")
      (value "SG73S2ATTD1101F")
      (footprint "RESC2013X60X30LL20T20")
      (fields (field (name "MANUFACTURER") "KOA Speer"))
      (libsource (lib "sub_1") (part "CMP-2001-02660-1"))
    )
    (comp (ref "r10")
      (value "SG73S2ATTD1101F")
      (footprint "RESC2013X60X30LL20T20")
      (fields (field (name "MANUFACTURER") "KOA Speer"))
      (libsource (lib "sub_1") (part "CMP-2001-02660-1"))
    )
    (comp (ref "r11")
      (value "SG73S2ATTD1101F")
      (footprint "RESC2013X60X30LL20T20")
      (fields (field (name "MANUFACTURER") "KOA Speer"))
      (libsource (lib "sub_1") (part "CMP-2001-02660-1"))
    )
    (comp (ref "r12")
      (value "SG73S2ATTD1101F")
      (footprint "RESC2013X60X30LL20T20")
      (fields (field (name "MANUFACTURER") "KOA Speer"))
      (libsource (lib "sub_1") (part "CMP-2001-02660-1"))
    )
    (comp (ref "r13")
      (value "SG73S2ATTD1101F")
      (footprint "RESC2013X60X30LL20T20")
      (fields (field (name "MANUFACTURER") "KOA Speer"))
      (libsource (lib "sub_1") (part "CMP-2001-02660-1"))
    )
    (comp (ref "r14")
      (value "SG73S2ATTD1101F")
      (footprint "RESC2013X60X30LL20T20")
      (fields (field (name "MANUFACTURER") "KOA Speer"))
      (libsource (lib "sub_1") (part "CMP-2001-02660-1"))
    )
    (comp (ref "r15")
      (value "SG73S2ATTD1101F")
      (footprint "RESC2013X60X30LL20T20")
      (fields (field (name "MANUFACTURER") "KOA Speer"))
      (libsource (lib "sub_1") (part "CMP-2001-02660-1"))
    )
    (comp (ref "r16")
      (value "SG73S2ATTD1101F")
      (footprint "RESC2013X60X30LL20T20")
      (fields (field (name "MANUFACTURER") "KOA Speer"))
      (libsource (lib "sub_1") (part "CMP-2001-02660-1"))
    )
    (comp (ref "r17")
      (value "SG73S2ATTD1101F")
      (footprint "RESC2013X60X30LL20T20")
      (fields (field (name "MANUFACTURER") "KOA Speer"))
      (libsource (lib "sub_1") (part "CMP-2001-02660-1"))
    )
    (comp (ref "r18")
      (value "SG73S2ATTD1101F")
      (footprint "RESC2013X60X30LL20T20")
      (fields (field (name "MANUFACTURER") "KOA Speer"))
      (libsource (lib "sub_1") (part "CMP-2001-02660-1"))
    )
    (comp (ref "r19")
      (value "SG73S2ATTD1101F")
      (footprint "RESC2013X60X30LL20T20")
      (fields (field (name "MANUFACTURER") "KOA Speer"))
      (libsource (lib "sub_1") (part "CMP-2001-02660-1"))
    )
    (comp (ref "r20")
      (value "SG73S2ATTD1101F")
      (footprint "RESC2013X60X30LL20T20")
      (fields (field (name "MANUFACTURER") "KOA Speer"))
      (libsource (lib "sub_1") (part "CMP-2001-02660-1"))
    )
    (comp (ref "r21")
      (value "SG73S2ATTD1101F")
      (footprint "RESC2013X60X30LL20T20")
      (fields (field (name "MANUFACTURER") "KOA Speer"))
      (libsource (lib "sub_1") (part "CMP-2001-02660-1"))
    )
    (comp (ref "r22")
      (value "SG73S2ATTD1101F")
      (footprint "RESC2013X60X30LL20T20")
      (fields (field (name "MANUFACTURER") "KOA Speer"))
      (libsource (lib "sub_1") (part "CMP-2001-02660-1"))
    )
    (comp (ref "r23")
      (value "SG73S2ATTD1101F")
      (footprint "RESC2013X60X30LL20T20")
      (fields (field (name "MANUFACTURER") "KOA Speer"))
      (libsource (lib "sub_1") (part "CMP-2001-02660-1"))
    )
    (comp (ref "r24")
      (value "SG73S2ATTD1101F")
      (footprint "RESC2013X60X30LL20T20")
      (fields (field (name "MANUFACTURER") "KOA Speer"))
      (libsource (lib "sub_1") (part "CMP-2001-02660-1"))
    )
    (comp (ref "r25")
      (value "SG73S2ATTD1101F")
      (footprint "RESC2013X60X30LL20T20")
      (fields (field (name "MANUFACTURER") "KOA Speer"))
      (libsource (lib "sub_1") (part "CMP-2001-02660-1"))
    )
    (comp (ref "r26")
      (value "SG73S2ATTD1101F")
      (footprint "RESC2013X60X30LL20T20")
      (fields (field (name "MANUFACTURER") "KOA Speer"))
      (libsource (lib "sub_1") (part "CMP-2001-02660-1"))
    )
    (comp (ref "r27")
      (value "SG73S2ATTD1101F")
      (footprint "RESC2013X60X30LL20T20")
      (fields (field (name "MANUFACTURER") "KOA Speer"))
      (libsource (lib "sub_1") (part "CMP-2001-02660-1"))
    )
    (comp (ref "r28")
      (value "SG73S2ATTD1101F")
      (footprint "RESC2013X60X30LL20T20")
      (fields (field (name "MANUFACTURER") "KOA Speer"))
      (libsource (lib "sub_1") (part "CMP-2001-02660-1"))
    )
    (comp (ref "r29")
      (value "SG73S2ATTD1101F")
      (footprint "RESC2013X60X30LL20T20")
      (fields (field (name "MANUFACTURER") "KOA Speer"))
      (libsource (lib "sub_1") (part "CMP-2001-02660-1"))
    )
    (comp (ref "r30")
      (value "SG73S2ATTD1101F")
      (footprint "RESC2013X60X30LL20T20")
      (fields (field (name "MANUFACTURER") "KOA Speer"))
      (libsource (lib "sub_1") (part "CMP-2001-02660-1"))
    )
    (comp (ref "r31")
      (value "SG73S2ATTD1101F")
      (footprint "RESC2013X60X30LL20T20")
      (fields (field (name "MANUFACTURER") "KOA Speer"))
      (libsource (lib "sub_1") (part "CMP-2001-02660-1"))
    )
    (comp (ref "r32")
      (value "SG73S2ATTD1101F")
      (footprint "RESC2013X60X30LL20T20")
      (fields (field (name "MANUFACTURER") "KOA Speer"))
      (libsource (lib "sub_1") (part "CMP-2001-02660-1"))
    )
    (comp (ref "r33")
      (value "SG73S2ATTD1101F")
      (footprint "RESC2013X60X30LL20T20")
      (fields (field (name "MANUFACTURER") "KOA Speer"))
      (libsource (lib "sub_1") (part "CMP-2001-02660-1"))
    )
    (comp (ref "r34")
      (value "SG73S2ATTD1101F")
      (footprint "RESC2013X60X30LL20T20")
      (fields (field (name "MANUFACTURER") "KOA Speer"))
      (libsource (lib "sub_1") (part "CMP-2001-02660-1"))
    )
    (comp (ref "r35")
      (value "SG73S2ATTD1101F")
      (footprint "RESC2013X60X30LL20T20")
      (fields (field (name "MANUFACTURER") "KOA Speer"))
      (libsource (lib "sub_1") (part "CMP-2001-02660-1"))
    )
    (comp (ref "r36")
      (value "SG73S2ATTD1101F")
      (footprint "RESC2013X60X30LL20T20")
      (fields (field (name "MANUFACTURER") "KOA Speer"))
      (libsource (lib "sub_1") (part "CMP-2001-02660-1"))
    )
    (comp (ref "r37")
      (value "SG73S2ATTD1101F")
      (footprint "RESC2013X60X30LL20T20")
      (fields (field (name "MANUFACTURER") "KOA Speer"))
      (libsource (lib "sub_1") (part "CMP-2001-02660-1"))
    )
    (comp (ref "r38")
      (value "SG73S2ATTD1101F")
      (footprint "RESC2013X60X30LL20T20")
      (fields (field (name "MANUFACTURER") "KOA Speer"))
      (libsource (lib "sub_1") (part "CMP-2001-02660-1"))
    )
    (comp (ref "r39")
      (value "SG73S2ATTD1101F")
      (footprint "RESC2013X60X30LL20T20")
      (fields (field (name "MANUFACTURER") "KOA Speer"))
      (libsource (lib "sub_1") (part "CMP-2001-02660-1"))
    )
    (comp (ref "rmcp1")
      (value "SG73S2ATTD1101F")
      (footprint "RESC2013X60X30LL20T20")
      (fields (field (name "MANUFACTURER") "KOA Speer"))
      (libsource (lib "midi_sub") (part "CMP-2001-02660-1"))
    )
    (comp (ref "rmcp2")
      (value "SG73S2ATTD1101F")
      (footprint "RESC2013X60X30LL20T20")
      (fields (field (name "MANUFACTURER") "KOA Speer"))
      (libsource (lib "midi_sub") (part "CMP-2001-02660-1"))
    )
  )
  (nets
    (net (code "1") (name "+5") (class "Default")
      (node (ref "10kR1") (pin "1") (pinfunction "1_1") (pintype "passive"))
      (node (ref "10kR2") (pin "2") (pinfunction "2_2") (pintype "passive"))
      (node (ref "3.3vto5v") (pin "1") (pinfunction "5Vo_1") (pintype "passive"))
      (node (ref "4067") (pin "24") (pinfunction "VCC_24") (pintype "passive"))
      (node (ref "C1") (pin "1") (pinfunction "1_1") (pintype "passive"))
      (node (ref "C10") (pin "1") (pinfunction "1_1") (pintype "passive"))
      (node (ref "C2") (pin "2") (pinfunction "2_2") (pintype "passive"))
      (node (ref "C3") (pin "1") (pinfunction "1_1") (pintype "passive"))
      (node (ref "C4") (pin "2") (pinfunction "2_2") (pintype "passive"))
      (node (ref "C5") (pin "1") (pinfunction "1_1") (pintype "passive"))
      (node (ref "C6") (pin "2") (pinfunction "2_2") (pintype "passive"))
      (node (ref "C7") (pin "1") (pinfunction "1_1") (pintype "passive"))
      (node (ref "C8") (pin "2") (pinfunction "2_2") (pintype "passive"))
      (node (ref "C9") (pin "2") (pinfunction "2_2") (pintype "passive"))
      (node (ref "esp32S2") (pin "VIN") (pinfunction "VIN_VIN") (pintype "passive"))
      (node (ref "max1") (pin "19") (pinfunction "V+_19") (pintype "passive"))
      (node (ref "max2") (pin "19") (pinfunction "V+_19") (pintype "passive"))
      (node (ref "max3") (pin "19") (pinfunction "V+_19") (pintype "passive"))
      (node (ref "max4") (pin "19") (pinfunction "V+_19") (pintype "passive"))
      (node (ref "mcp1") (pin "9") (pinfunction "VDD_9") (pintype "passive"))
      (node (ref "mcp2") (pin "15") (pinfunction "A0_15") (pintype "passive"))
      (node (ref "mcp2") (pin "9") (pinfunction "VDD_9") (pintype "passive"))
      (node (ref "r1") (pin "2") (pinfunction "2_2") (pintype "passive"))
      (node (ref "r10") (pin "2") (pinfunction "2_2") (pintype "passive"))
      (node (ref "r11") (pin "2") (pinfunction "2_2") (pintype "passive"))
      (node (ref "r12") (pin "2") (pinfunction "2_2") (pintype "passive"))
      (node (ref "r13") (pin "2") (pinfunction "2_2") (pintype "passive"))
      (node (ref "r14") (pin "2") (pinfunction "2_2") (pintype "passive"))
      (node (ref "r15") (pin "2") (pinfunction "2_2") (pintype "passive"))
      (node (ref "r16") (pin "2") (pinfunction "2_2") (pintype "passive"))
      (node (ref "r17") (pin "2") (pinfunction "2_2") (pintype "passive"))
      (node (ref "r18") (pin "2") (pinfunction "2_2") (pintype "passive"))
      (node (ref "r19") (pin "2") (pinfunction "2_2") (pintype "passive"))
      (node (ref "r2") (pin "2") (pinfunction "2_2") (pintype "passive"))
      (node (ref "r20") (pin "2") (pinfunction "2_2") (pintype "passive"))
      (node (ref "r21") (pin "2") (pinfunction "2_2") (pintype "passive"))
      (node (ref "r22") (pin "2") (pinfunction "2_2") (pintype "passive"))
      (node (ref "r23") (pin "2") (pinfunction "2_2") (pintype "passive"))
      (node (ref "r24") (pin "2") (pinfunction "2_2") (pintype "passive"))
      (node (ref "r25") (pin "2") (pinfunction "2_2") (pintype "passive"))
      (node (ref "r26") (pin "2") (pinfunction "2_2") (pintype "passive"))
      (node (ref "r27") (pin "2") (pinfunction "2_2") (pintype "passive"))
      (node (ref "r28") (pin "2") (pinfunction "2_2") (pintype "passive"))
      (node (ref "r29") (pin "2") (pinfunction "2_2") (pintype "passive"))
      (node (ref "r3") (pin "2") (pinfunction "2_2") (pintype "passive"))
      (node (ref "r30") (pin "2") (pinfunction "2_2") (pintype "passive"))
      (node (ref "r31") (pin "2") (pinfunction "2_2") (pintype "passive"))
      (node (ref "r32") (pin "2") (pinfunction "2_2") (pintype "passive"))
      (node (ref "r33") (pin "2") (pinfunction "2_2") (pintype "passive"))
      (node (ref "r34") (pin "2") (pinfunction "2_2") (pintype "passive"))
      (node (ref "r35") (pin "2") (pinfunction "2_2") (pintype "passive"))
      (node (ref "r36") (pin "2") (pinfunction "2_2") (pintype "passive"))
      (node (ref "r37") (pin "2") (pinfunction "2_2") (pintype "passive"))
      (node (ref "r38") (pin "2") (pinfunction "2_2") (pintype "passive"))
      (node (ref "r39") (pin "2") (pinfunction "2_2") (pintype "passive"))
      (node (ref "r4") (pin "2") (pinfunction "2_2") (pintype "passive"))
      (node (ref "r5") (pin "2") (pinfunction "2_2") (pintype "passive"))
      (node (ref "r6") (pin "2") (pinfunction "2_2") (pintype "passive"))
      (node (ref "r8") (pin "2") (pinfunction "2_2") (pintype "passive"))
      (node (ref "r9") (pin "2") (pinfunction "2_2") (pintype "passive"))
      (node (ref "rmcp1") (pin "2") (pinfunction "2_2") (pintype "passive"))
      (node (ref "rmcp2") (pin "2") (pinfunction "2_2") (pintype "passive"))
    )
    (net (code "2") (name "/3.3v") (class "Default")
      (node (ref "3.3vto5v") (pin "3") (pinfunction "3.3Vin_3") (pintype "passive"))
      (node (ref "C11") (pin "2") (pinfunction "2_2") (pintype "passive"))
      (node (ref "esp32S3") (pin "21") (pinfunction "3.3v_21") (pintype "passive"))
    )
    (net (code "3") (name "/b0") (class "Default")
      (node (ref "4067") (pin "9") (pinfunction "Y0_9") (pintype "passive"))
      (node (ref "ALPS EC1") (pin "S1") (pinfunction "S1_S1") (pintype "passive"))
    )
    (net (code "4") (name "/b1") (class "Default")
      (node (ref "4067") (pin "8") (pinfunction "Y1_8") (pintype "passive"))
      (node (ref "ALPS EC2") (pin "S1") (pinfunction "S1_S1") (pintype "passive"))
    )
    (net (code "5") (name "/b2") (class "Default")
      (node (ref "4067") (pin "7") (pinfunction "Y2_7") (pintype "passive"))
      (node (ref "ALPS EC3") (pin "S1") (pinfunction "S1_S1") (pintype "passive"))
    )
    (net (code "6") (name "/b3") (class "Default")
      (node (ref "4067") (pin "6") (pinfunction "Y3_6") (pintype "passive"))
      (node (ref "ALPS EC4") (pin "S1") (pinfunction "S1_S1") (pintype "passive"))
    )
    (net (code "7") (name "/b4") (class "Default")
      (node (ref "4067") (pin "5") (pinfunction "Y4_5") (pintype "passive"))
      (node (ref "ALPS EC5") (pin "S1") (pinfunction "S1_S1") (pintype "passive"))
    )
    (net (code "8") (name "/b5") (class "Default")
      (node (ref "4067") (pin "4") (pinfunction "Y5_4") (pintype "passive"))
      (node (ref "ALPS EC6") (pin "S1") (pinfunction "S1_S1") (pintype "passive"))
    )
    (net (code "9") (name "/b6") (class "Default")
      (node (ref "4067") (pin "3") (pinfunction "Y6_3") (pintype "passive"))
      (node (ref "ALPS EC7") (pin "S1") (pinfunction "S1_S1") (pintype "passive"))
    )
    (net (code "10") (name "/b7") (class "Default")
      (node (ref "4067") (pin "2") (pinfunction "Y7_2") (pintype "passive"))
      (node (ref "ALPS EC8") (pin "S1") (pinfunction "S1_S1") (pintype "passive"))
    )
    (net (code "11") (name "/b8") (class "Default")
      (node (ref "4067") (pin "23") (pinfunction "Y8_23") (pintype "passive"))
      (node (ref "ALPS EC9") (pin "S1") (pinfunction "S1_S1") (pintype "passive"))
    )
    (net (code "12") (name "/b9") (class "Default")
      (node (ref "4067") (pin "22") (pinfunction "Y9_22") (pintype "passive"))
      (node (ref "ALPS EC10") (pin "S1") (pinfunction "S1_S1") (pintype "passive"))
    )
    (net (code "13") (name "/b10") (class "Default")
      (node (ref "4067") (pin "21") (pinfunction "Y10_21") (pintype "passive"))
      (node (ref "ALPS EC11") (pin "S1") (pinfunction "S1_S1") (pintype "passive"))
    )
    (net (code "14") (name "/b11") (class "Default")
      (node (ref "4067") (pin "20") (pinfunction "Y11_20") (pintype "passive"))
      (node (ref "ALPS EC12") (pin "S1") (pinfunction "S1_S1") (pintype "passive"))
    )
    (net (code "15") (name "/b12") (class "Default")
      (node (ref "4067") (pin "19") (pinfunction "Y12_19") (pintype "passive"))
      (node (ref "ALPS EC13") (pin "S1") (pinfunction "S1_S1") (pintype "passive"))
    )
    (net (code "16") (name "/b13") (class "Default")
      (node (ref "4067") (pin "18") (pinfunction "Y13_18") (pintype "passive"))
      (node (ref "ALPS EC14") (pin "S1") (pinfunction "S1_S1") (pintype "passive"))
    )
    (net (code "17") (name "/b14") (class "Default")
      (node (ref "4067") (pin "17") (pinfunction "Y14_17") (pintype "passive"))
      (node (ref "ALPS EC15") (pin "S1") (pinfunction "S1_S1") (pintype "passive"))
    )
    (net (code "18") (name "/b15") (class "Default")
      (node (ref "4067") (pin "16") (pinfunction "Y15_16") (pintype "passive"))
      (node (ref "ALPS EC16") (pin "S1") (pinfunction "S1_S1") (pintype "passive"))
    )
    (net (code "19") (name "/c1_1") (class "Default")
      (node (ref "*led1") (pin "2") (pinfunction "2_2") (pintype "passive"))
      (node (ref "*led17") (pin "2") (pinfunction "2_2") (pintype "passive"))
      (node (ref "*led25") (pin "2") (pinfunction "2_2") (pintype "passive"))
      (node (ref "*led33") (pin "2") (pinfunction "2_2") (pintype "passive"))
      (node (ref "*led41") (pin "2") (pinfunction "2_2") (pintype "passive"))
      (node (ref "*led49") (pin "2") (pinfunction "2_2") (pintype "passive"))
      (node (ref "*led57") (pin "2") (pinfunction "2_2") (pintype "passive"))
      (node (ref "*led9") (pin "2") (pinfunction "2_2") (pintype "passive"))
      (node (ref "max1") (pin "22") (pinfunction "SEGDP_22") (pintype "passive"))
    )
    (net (code "20") (name "/c1_2") (class "Default")
      (node (ref "*led10") (pin "2") (pinfunction "2_2") (pintype "passive"))
      (node (ref "*led18") (pin "2") (pinfunction "2_2") (pintype "passive"))
      (node (ref "*led2") (pin "2") (pinfunction "2_2") (pintype "passive"))
      (node (ref "*led26") (pin "2") (pinfunction "2_2") (pintype "passive"))
      (node (ref "*led34") (pin "2") (pinfunction "2_2") (pintype "passive"))
      (node (ref "*led42") (pin "2") (pinfunction "2_2") (pintype "passive"))
      (node (ref "*led50") (pin "2") (pinfunction "2_2") (pintype "passive"))
      (node (ref "*led58") (pin "2") (pinfunction "2_2") (pintype "passive"))
      (node (ref "max1") (pin "14") (pinfunction "SEGA_14") (pintype "passive"))
    )
    (net (code "21") (name "/c1_3") (class "Default")
      (node (ref "*led11") (pin "2") (pinfunction "2_2") (pintype "passive"))
      (node (ref "*led19") (pin "2") (pinfunction "2_2") (pintype "passive"))
      (node (ref "*led27") (pin "2") (pinfunction "2_2") (pintype "passive"))
      (node (ref "*led3") (pin "2") (pinfunction "2_2") (pintype "passive"))
      (node (ref "*led35") (pin "2") (pinfunction "2_2") (pintype "passive"))
      (node (ref "*led43") (pin "2") (pinfunction "2_2") (pintype "passive"))
      (node (ref "*led51") (pin "2") (pinfunction "2_2") (pintype "passive"))
      (node (ref "*led59") (pin "2") (pinfunction "2_2") (pintype "passive"))
      (node (ref "max1") (pin "16") (pinfunction "SEGB_16") (pintype "passive"))
    )
    (net (code "22") (name "/c1_4") (class "Default")
      (node (ref "*led12") (pin "2") (pinfunction "2_2") (pintype "passive"))
      (node (ref "*led20") (pin "2") (pinfunction "2_2") (pintype "passive"))
      (node (ref "*led28") (pin "2") (pinfunction "2_2") (pintype "passive"))
      (node (ref "*led36") (pin "2") (pinfunction "2_2") (pintype "passive"))
      (node (ref "*led4") (pin "2") (pinfunction "2_2") (pintype "passive"))
      (node (ref "*led44") (pin "2") (pinfunction "2_2") (pintype "passive"))
      (node (ref "*led52") (pin "2") (pinfunction "2_2") (pintype "passive"))
      (node (ref "*led60") (pin "2") (pinfunction "2_2") (pintype "passive"))
      (node (ref "max1") (pin "20") (pinfunction "SEGC_20") (pintype "passive"))
    )
    (net (code "23") (name "/c1_5") (class "Default")
      (node (ref "*led13") (pin "2") (pinfunction "2_2") (pintype "passive"))
      (node (ref "*led21") (pin "2") (pinfunction "2_2") (pintype "passive"))
      (node (ref "*led29") (pin "2") (pinfunction "2_2") (pintype "passive"))
      (node (ref "*led37") (pin "2") (pinfunction "2_2") (pintype "passive"))
      (node (ref "*led45") (pin "2") (pinfunction "2_2") (pintype "passive"))
      (node (ref "*led5") (pin "2") (pinfunction "2_2") (pintype "passive"))
      (node (ref "*led53") (pin "2") (pinfunction "2_2") (pintype "passive"))
      (node (ref "*led61") (pin "2") (pinfunction "2_2") (pintype "passive"))
      (node (ref "max1") (pin "23") (pinfunction "SEGD_23") (pintype "passive"))
    )
    (net (code "24") (name "/c1_6") (class "Default")
      (node (ref "*led14") (pin "2") (pinfunction "2_2") (pintype "passive"))
      (node (ref "*led22") (pin "2") (pinfunction "2_2") (pintype "passive"))
      (node (ref "*led30") (pin "2") (pinfunction "2_2") (pintype "passive"))
      (node (ref "*led38") (pin "2") (pinfunction "2_2") (pintype "passive"))
      (node (ref "*led46") (pin "2") (pinfunction "2_2") (pintype "passive"))
      (node (ref "*led54") (pin "2") (pinfunction "2_2") (pintype "passive"))
      (node (ref "*led6") (pin "2") (pinfunction "2_2") (pintype "passive"))
      (node (ref "*led62") (pin "2") (pinfunction "2_2") (pintype "passive"))
      (node (ref "max1") (pin "21") (pinfunction "SEGE_21") (pintype "passive"))
    )
    (net (code "25") (name "/c1_7") (class "Default")
      (node (ref "*led15") (pin "2") (pinfunction "2_2") (pintype "passive"))
      (node (ref "*led23") (pin "2") (pinfunction "2_2") (pintype "passive"))
      (node (ref "*led31") (pin "2") (pinfunction "2_2") (pintype "passive"))
      (node (ref "*led39") (pin "2") (pinfunction "2_2") (pintype "passive"))
      (node (ref "*led47") (pin "2") (pinfunction "2_2") (pintype "passive"))
      (node (ref "*led55") (pin "2") (pinfunction "2_2") (pintype "passive"))
      (node (ref "*led63") (pin "2") (pinfunction "2_2") (pintype "passive"))
      (node (ref "*led7") (pin "2") (pinfunction "2_2") (pintype "passive"))
      (node (ref "max1") (pin "15") (pinfunction "SEGF_15") (pintype "passive"))
    )
    (net (code "26") (name "/c1_8") (class "Default")
      (node (ref "*led16") (pin "2") (pinfunction "2_2") (pintype "passive"))
      (node (ref "*led24") (pin "2") (pinfunction "2_2") (pintype "passive"))
      (node (ref "*led32") (pin "2") (pinfunction "2_2") (pintype "passive"))
      (node (ref "*led40") (pin "2") (pinfunction "2_2") (pintype "passive"))
      (node (ref "*led48") (pin "2") (pinfunction "2_2") (pintype "passive"))
      (node (ref "*led56") (pin "2") (pinfunction "2_2") (pintype "passive"))
      (node (ref "*led64") (pin "2") (pinfunction "2_2") (pintype "passive"))
      (node (ref "*led8") (pin "2") (pinfunction "2_2") (pintype "passive"))
      (node (ref "max1") (pin "17") (pinfunction "SEGG_17") (pintype "passive"))
    )
    (net (code "27") (name "/c2_1") (class "Default")
      (node (ref "*led105") (pin "2") (pinfunction "2_2") (pintype "passive"))
      (node (ref "*led113") (pin "2") (pinfunction "2_2") (pintype "passive"))
      (node (ref "*led121") (pin "2") (pinfunction "2_2") (pintype "passive"))
      (node (ref "*led65") (pin "2") (pinfunction "2_2") (pintype "passive"))
      (node (ref "*led73") (pin "2") (pinfunction "2_2") (pintype "passive"))
      (node (ref "*led81") (pin "2") (pinfunction "2_2") (pintype "passive"))
      (node (ref "*led89") (pin "2") (pinfunction "2_2") (pintype "passive"))
      (node (ref "*led97") (pin "2") (pinfunction "2_2") (pintype "passive"))
      (node (ref "max2") (pin "22") (pinfunction "SEGDP_22") (pintype "passive"))
    )
    (net (code "28") (name "/c2_2") (class "Default")
      (node (ref "*led106") (pin "2") (pinfunction "2_2") (pintype "passive"))
      (node (ref "*led114") (pin "2") (pinfunction "2_2") (pintype "passive"))
      (node (ref "*led122") (pin "2") (pinfunction "2_2") (pintype "passive"))
      (node (ref "*led66") (pin "2") (pinfunction "2_2") (pintype "passive"))
      (node (ref "*led74") (pin "2") (pinfunction "2_2") (pintype "passive"))
      (node (ref "*led82") (pin "2") (pinfunction "2_2") (pintype "passive"))
      (node (ref "*led90") (pin "2") (pinfunction "2_2") (pintype "passive"))
      (node (ref "*led98") (pin "2") (pinfunction "2_2") (pintype "passive"))
      (node (ref "max2") (pin "14") (pinfunction "SEGA_14") (pintype "passive"))
    )
    (net (code "29") (name "/c2_3") (class "Default")
      (node (ref "*led107") (pin "2") (pinfunction "2_2") (pintype "passive"))
      (node (ref "*led115") (pin "2") (pinfunction "2_2") (pintype "passive"))
      (node (ref "*led123") (pin "2") (pinfunction "2_2") (pintype "passive"))
      (node (ref "*led67") (pin "2") (pinfunction "2_2") (pintype "passive"))
      (node (ref "*led75") (pin "2") (pinfunction "2_2") (pintype "passive"))
      (node (ref "*led83") (pin "2") (pinfunction "2_2") (pintype "passive"))
      (node (ref "*led91") (pin "2") (pinfunction "2_2") (pintype "passive"))
      (node (ref "*led99") (pin "2") (pinfunction "2_2") (pintype "passive"))
      (node (ref "max2") (pin "16") (pinfunction "SEGB_16") (pintype "passive"))
    )
    (net (code "30") (name "/c2_4") (class "Default")
      (node (ref "*led100") (pin "2") (pinfunction "2_2") (pintype "passive"))
      (node (ref "*led108") (pin "2") (pinfunction "2_2") (pintype "passive"))
      (node (ref "*led116") (pin "2") (pinfunction "2_2") (pintype "passive"))
      (node (ref "*led124") (pin "2") (pinfunction "2_2") (pintype "passive"))
      (node (ref "*led68") (pin "2") (pinfunction "2_2") (pintype "passive"))
      (node (ref "*led76") (pin "2") (pinfunction "2_2") (pintype "passive"))
      (node (ref "*led84") (pin "2") (pinfunction "2_2") (pintype "passive"))
      (node (ref "*led92") (pin "2") (pinfunction "2_2") (pintype "passive"))
      (node (ref "max2") (pin "20") (pinfunction "SEGC_20") (pintype "passive"))
    )
    (net (code "31") (name "/c2_5") (class "Default")
      (node (ref "*led101") (pin "2") (pinfunction "2_2") (pintype "passive"))
      (node (ref "*led109") (pin "2") (pinfunction "2_2") (pintype "passive"))
      (node (ref "*led117") (pin "2") (pinfunction "2_2") (pintype "passive"))
      (node (ref "*led125") (pin "2") (pinfunction "2_2") (pintype "passive"))
      (node (ref "*led69") (pin "2") (pinfunction "2_2") (pintype "passive"))
      (node (ref "*led77") (pin "2") (pinfunction "2_2") (pintype "passive"))
      (node (ref "*led85") (pin "2") (pinfunction "2_2") (pintype "passive"))
      (node (ref "*led93") (pin "2") (pinfunction "2_2") (pintype "passive"))
      (node (ref "max2") (pin "23") (pinfunction "SEGD_23") (pintype "passive"))
    )
    (net (code "32") (name "/c2_6") (class "Default")
      (node (ref "*led102") (pin "2") (pinfunction "2_2") (pintype "passive"))
      (node (ref "*led110") (pin "2") (pinfunction "2_2") (pintype "passive"))
      (node (ref "*led118") (pin "2") (pinfunction "2_2") (pintype "passive"))
      (node (ref "*led126") (pin "2") (pinfunction "2_2") (pintype "passive"))
      (node (ref "*led70") (pin "2") (pinfunction "2_2") (pintype "passive"))
      (node (ref "*led78") (pin "2") (pinfunction "2_2") (pintype "passive"))
      (node (ref "*led86") (pin "2") (pinfunction "2_2") (pintype "passive"))
      (node (ref "*led94") (pin "2") (pinfunction "2_2") (pintype "passive"))
      (node (ref "max2") (pin "21") (pinfunction "SEGE_21") (pintype "passive"))
    )
    (net (code "33") (name "/c2_7") (class "Default")
      (node (ref "*led103") (pin "2") (pinfunction "2_2") (pintype "passive"))
      (node (ref "*led111") (pin "2") (pinfunction "2_2") (pintype "passive"))
      (node (ref "*led119") (pin "2") (pinfunction "2_2") (pintype "passive"))
      (node (ref "*led127") (pin "2") (pinfunction "2_2") (pintype "passive"))
      (node (ref "*led71") (pin "2") (pinfunction "2_2") (pintype "passive"))
      (node (ref "*led79") (pin "2") (pinfunction "2_2") (pintype "passive"))
      (node (ref "*led87") (pin "2") (pinfunction "2_2") (pintype "passive"))
      (node (ref "*led95") (pin "2") (pinfunction "2_2") (pintype "passive"))
      (node (ref "max2") (pin "15") (pinfunction "SEGF_15") (pintype "passive"))
    )
    (net (code "34") (name "/c2_8") (class "Default")
      (node (ref "*led104") (pin "2") (pinfunction "2_2") (pintype "passive"))
      (node (ref "*led112") (pin "2") (pinfunction "2_2") (pintype "passive"))
      (node (ref "*led120") (pin "2") (pinfunction "2_2") (pintype "passive"))
      (node (ref "*led128") (pin "2") (pinfunction "2_2") (pintype "passive"))
      (node (ref "*led72") (pin "2") (pinfunction "2_2") (pintype "passive"))
      (node (ref "*led80") (pin "2") (pinfunction "2_2") (pintype "passive"))
      (node (ref "*led88") (pin "2") (pinfunction "2_2") (pintype "passive"))
      (node (ref "*led96") (pin "2") (pinfunction "2_2") (pintype "passive"))
      (node (ref "max2") (pin "17") (pinfunction "SEGG_17") (pintype "passive"))
    )
    (net (code "35") (name "/c3_1") (class "Default")
      (node (ref "*led129") (pin "2") (pinfunction "2_2") (pintype "passive"))
      (node (ref "*led137") (pin "2") (pinfunction "2_2") (pintype "passive"))
      (node (ref "*led145") (pin "2") (pinfunction "2_2") (pintype "passive"))
      (node (ref "*led153") (pin "2") (pinfunction "2_2") (pintype "passive"))
      (node (ref "*led161") (pin "2") (pinfunction "2_2") (pintype "passive"))
      (node (ref "*led169") (pin "2") (pinfunction "2_2") (pintype "passive"))
      (node (ref "*led177") (pin "2") (pinfunction "2_2") (pintype "passive"))
      (node (ref "*led185") (pin "2") (pinfunction "2_2") (pintype "passive"))
      (node (ref "max3") (pin "22") (pinfunction "SEGDP_22") (pintype "passive"))
    )
    (net (code "36") (name "/c3_2") (class "Default")
      (node (ref "*led130") (pin "2") (pinfunction "2_2") (pintype "passive"))
      (node (ref "*led138") (pin "2") (pinfunction "2_2") (pintype "passive"))
      (node (ref "*led146") (pin "2") (pinfunction "2_2") (pintype "passive"))
      (node (ref "*led154") (pin "2") (pinfunction "2_2") (pintype "passive"))
      (node (ref "*led162") (pin "2") (pinfunction "2_2") (pintype "passive"))
      (node (ref "*led170") (pin "2") (pinfunction "2_2") (pintype "passive"))
      (node (ref "*led178") (pin "2") (pinfunction "2_2") (pintype "passive"))
      (node (ref "*led186") (pin "2") (pinfunction "2_2") (pintype "passive"))
      (node (ref "max3") (pin "14") (pinfunction "SEGA_14") (pintype "passive"))
    )
    (net (code "37") (name "/c3_3") (class "Default")
      (node (ref "*led131") (pin "2") (pinfunction "2_2") (pintype "passive"))
      (node (ref "*led139") (pin "2") (pinfunction "2_2") (pintype "passive"))
      (node (ref "*led147") (pin "2") (pinfunction "2_2") (pintype "passive"))
      (node (ref "*led155") (pin "2") (pinfunction "2_2") (pintype "passive"))
      (node (ref "*led163") (pin "2") (pinfunction "2_2") (pintype "passive"))
      (node (ref "*led171") (pin "2") (pinfunction "2_2") (pintype "passive"))
      (node (ref "*led179") (pin "2") (pinfunction "2_2") (pintype "passive"))
      (node (ref "*led187") (pin "2") (pinfunction "2_2") (pintype "passive"))
      (node (ref "max3") (pin "16") (pinfunction "SEGB_16") (pintype "passive"))
    )
    (net (code "38") (name "/c3_4") (class "Default")
      (node (ref "*led132") (pin "2") (pinfunction "2_2") (pintype "passive"))
      (node (ref "*led140") (pin "2") (pinfunction "2_2") (pintype "passive"))
      (node (ref "*led148") (pin "2") (pinfunction "2_2") (pintype "passive"))
      (node (ref "*led156") (pin "2") (pinfunction "2_2") (pintype "passive"))
      (node (ref "*led164") (pin "2") (pinfunction "2_2") (pintype "passive"))
      (node (ref "*led172") (pin "2") (pinfunction "2_2") (pintype "passive"))
      (node (ref "*led180") (pin "2") (pinfunction "2_2") (pintype "passive"))
      (node (ref "*led188") (pin "2") (pinfunction "2_2") (pintype "passive"))
      (node (ref "max3") (pin "20") (pinfunction "SEGC_20") (pintype "passive"))
    )
    (net (code "39") (name "/c3_5") (class "Default")
      (node (ref "*led133") (pin "2") (pinfunction "2_2") (pintype "passive"))
      (node (ref "*led141") (pin "2") (pinfunction "2_2") (pintype "passive"))
      (node (ref "*led149") (pin "2") (pinfunction "2_2") (pintype "passive"))
      (node (ref "*led157") (pin "2") (pinfunction "2_2") (pintype "passive"))
      (node (ref "*led165") (pin "2") (pinfunction "2_2") (pintype "passive"))
      (node (ref "*led173") (pin "2") (pinfunction "2_2") (pintype "passive"))
      (node (ref "*led181") (pin "2") (pinfunction "2_2") (pintype "passive"))
      (node (ref "*led189") (pin "2") (pinfunction "2_2") (pintype "passive"))
      (node (ref "max3") (pin "23") (pinfunction "SEGD_23") (pintype "passive"))
    )
    (net (code "40") (name "/c3_6") (class "Default")
      (node (ref "*led134") (pin "2") (pinfunction "2_2") (pintype "passive"))
      (node (ref "*led142") (pin "2") (pinfunction "2_2") (pintype "passive"))
      (node (ref "*led150") (pin "2") (pinfunction "2_2") (pintype "passive"))
      (node (ref "*led158") (pin "2") (pinfunction "2_2") (pintype "passive"))
      (node (ref "*led166") (pin "2") (pinfunction "2_2") (pintype "passive"))
      (node (ref "*led174") (pin "2") (pinfunction "2_2") (pintype "passive"))
      (node (ref "*led182") (pin "2") (pinfunction "2_2") (pintype "passive"))
      (node (ref "*led190") (pin "2") (pinfunction "2_2") (pintype "passive"))
      (node (ref "max3") (pin "21") (pinfunction "SEGE_21") (pintype "passive"))
    )
    (net (code "41") (name "/c3_7") (class "Default")
      (node (ref "*led135") (pin "2") (pinfunction "2_2") (pintype "passive"))
      (node (ref "*led143") (pin "2") (pinfunction "2_2") (pintype "passive"))
      (node (ref "*led151") (pin "2") (pinfunction "2_2") (pintype "passive"))
      (node (ref "*led159") (pin "2") (pinfunction "2_2") (pintype "passive"))
      (node (ref "*led167") (pin "2") (pinfunction "2_2") (pintype "passive"))
      (node (ref "*led175") (pin "2") (pinfunction "2_2") (pintype "passive"))
      (node (ref "*led183") (pin "2") (pinfunction "2_2") (pintype "passive"))
      (node (ref "*led191") (pin "2") (pinfunction "2_2") (pintype "passive"))
      (node (ref "max3") (pin "15") (pinfunction "SEGF_15") (pintype "passive"))
    )
    (net (code "42") (name "/c3_8") (class "Default")
      (node (ref "*led136") (pin "2") (pinfunction "2_2") (pintype "passive"))
      (node (ref "*led144") (pin "2") (pinfunction "2_2") (pintype "passive"))
      (node (ref "*led152") (pin "2") (pinfunction "2_2") (pintype "passive"))
      (node (ref "*led160") (pin "2") (pinfunction "2_2") (pintype "passive"))
      (node (ref "*led168") (pin "2") (pinfunction "2_2") (pintype "passive"))
      (node (ref "*led176") (pin "2") (pinfunction "2_2") (pintype "passive"))
      (node (ref "*led184") (pin "2") (pinfunction "2_2") (pintype "passive"))
      (node (ref "*led192") (pin "2") (pinfunction "2_2") (pintype "passive"))
      (node (ref "max3") (pin "17") (pinfunction "SEGG_17") (pintype "passive"))
    )
    (net (code "43") (name "/c4_1") (class "Default")
      (node (ref "*led193") (pin "2") (pinfunction "2_2") (pintype "passive"))
      (node (ref "*led201") (pin "2") (pinfunction "2_2") (pintype "passive"))
      (node (ref "*led209") (pin "2") (pinfunction "2_2") (pintype "passive"))
      (node (ref "*led217") (pin "2") (pinfunction "2_2") (pintype "passive"))
      (node (ref "*led225") (pin "2") (pinfunction "2_2") (pintype "passive"))
      (node (ref "*led233") (pin "2") (pinfunction "2_2") (pintype "passive"))
      (node (ref "*led241") (pin "2") (pinfunction "2_2") (pintype "passive"))
      (node (ref "*led249") (pin "2") (pinfunction "2_2") (pintype "passive"))
      (node (ref "max4") (pin "22") (pinfunction "SEGDP_22") (pintype "passive"))
    )
    (net (code "44") (name "/c4_2") (class "Default")
      (node (ref "*led194") (pin "2") (pinfunction "2_2") (pintype "passive"))
      (node (ref "*led202") (pin "2") (pinfunction "2_2") (pintype "passive"))
      (node (ref "*led210") (pin "2") (pinfunction "2_2") (pintype "passive"))
      (node (ref "*led218") (pin "2") (pinfunction "2_2") (pintype "passive"))
      (node (ref "*led226") (pin "2") (pinfunction "2_2") (pintype "passive"))
      (node (ref "*led234") (pin "2") (pinfunction "2_2") (pintype "passive"))
      (node (ref "*led242") (pin "2") (pinfunction "2_2") (pintype "passive"))
      (node (ref "*led250") (pin "2") (pinfunction "2_2") (pintype "passive"))
      (node (ref "max4") (pin "14") (pinfunction "SEGA_14") (pintype "passive"))
    )
    (net (code "45") (name "/c4_3") (class "Default")
      (node (ref "*led195") (pin "2") (pinfunction "2_2") (pintype "passive"))
      (node (ref "*led203") (pin "2") (pinfunction "2_2") (pintype "passive"))
      (node (ref "*led211") (pin "2") (pinfunction "2_2") (pintype "passive"))
      (node (ref "*led219") (pin "2") (pinfunction "2_2") (pintype "passive"))
      (node (ref "*led227") (pin "2") (pinfunction "2_2") (pintype "passive"))
      (node (ref "*led235") (pin "2") (pinfunction "2_2") (pintype "passive"))
      (node (ref "*led243") (pin "2") (pinfunction "2_2") (pintype "passive"))
      (node (ref "*led251") (pin "2") (pinfunction "2_2") (pintype "passive"))
      (node (ref "max4") (pin "16") (pinfunction "SEGB_16") (pintype "passive"))
    )
    (net (code "46") (name "/c4_4") (class "Default")
      (node (ref "*led196") (pin "2") (pinfunction "2_2") (pintype "passive"))
      (node (ref "*led204") (pin "2") (pinfunction "2_2") (pintype "passive"))
      (node (ref "*led212") (pin "2") (pinfunction "2_2") (pintype "passive"))
      (node (ref "*led220") (pin "2") (pinfunction "2_2") (pintype "passive"))
      (node (ref "*led228") (pin "2") (pinfunction "2_2") (pintype "passive"))
      (node (ref "*led236") (pin "2") (pinfunction "2_2") (pintype "passive"))
      (node (ref "*led244") (pin "2") (pinfunction "2_2") (pintype "passive"))
      (node (ref "*led252") (pin "2") (pinfunction "2_2") (pintype "passive"))
      (node (ref "max4") (pin "20") (pinfunction "SEGC_20") (pintype "passive"))
    )
    (net (code "47") (name "/c4_5") (class "Default")
      (node (ref "*led197") (pin "2") (pinfunction "2_2") (pintype "passive"))
      (node (ref "*led205") (pin "2") (pinfunction "2_2") (pintype "passive"))
      (node (ref "*led213") (pin "2") (pinfunction "2_2") (pintype "passive"))
      (node (ref "*led221") (pin "2") (pinfunction "2_2") (pintype "passive"))
      (node (ref "*led229") (pin "2") (pinfunction "2_2") (pintype "passive"))
      (node (ref "*led237") (pin "2") (pinfunction "2_2") (pintype "passive"))
      (node (ref "*led245") (pin "2") (pinfunction "2_2") (pintype "passive"))
      (node (ref "*led253") (pin "2") (pinfunction "2_2") (pintype "passive"))
      (node (ref "max4") (pin "23") (pinfunction "SEGD_23") (pintype "passive"))
    )
    (net (code "48") (name "/c4_6") (class "Default")
      (node (ref "*led198") (pin "2") (pinfunction "2_2") (pintype "passive"))
      (node (ref "*led206") (pin "2") (pinfunction "2_2") (pintype "passive"))
      (node (ref "*led214") (pin "2") (pinfunction "2_2") (pintype "passive"))
      (node (ref "*led222") (pin "2") (pinfunction "2_2") (pintype "passive"))
      (node (ref "*led230") (pin "2") (pinfunction "2_2") (pintype "passive"))
      (node (ref "*led238") (pin "2") (pinfunction "2_2") (pintype "passive"))
      (node (ref "*led246") (pin "2") (pinfunction "2_2") (pintype "passive"))
      (node (ref "*led254") (pin "2") (pinfunction "2_2") (pintype "passive"))
      (node (ref "max4") (pin "21") (pinfunction "SEGE_21") (pintype "passive"))
    )
    (net (code "49") (name "/c4_7") (class "Default")
      (node (ref "*led199") (pin "2") (pinfunction "2_2") (pintype "passive"))
      (node (ref "*led207") (pin "2") (pinfunction "2_2") (pintype "passive"))
      (node (ref "*led215") (pin "2") (pinfunction "2_2") (pintype "passive"))
      (node (ref "*led223") (pin "2") (pinfunction "2_2") (pintype "passive"))
      (node (ref "*led231") (pin "2") (pinfunction "2_2") (pintype "passive"))
      (node (ref "*led239") (pin "2") (pinfunction "2_2") (pintype "passive"))
      (node (ref "*led247") (pin "2") (pinfunction "2_2") (pintype "passive"))
      (node (ref "*led255") (pin "2") (pinfunction "2_2") (pintype "passive"))
      (node (ref "max4") (pin "15") (pinfunction "SEGF_15") (pintype "passive"))
    )
    (net (code "50") (name "/c4_8") (class "Default")
      (node (ref "*led200") (pin "2") (pinfunction "2_2") (pintype "passive"))
      (node (ref "*led208") (pin "2") (pinfunction "2_2") (pintype "passive"))
      (node (ref "*led216") (pin "2") (pinfunction "2_2") (pintype "passive"))
      (node (ref "*led224") (pin "2") (pinfunction "2_2") (pintype "passive"))
      (node (ref "*led232") (pin "2") (pinfunction "2_2") (pintype "passive"))
      (node (ref "*led240") (pin "2") (pinfunction "2_2") (pintype "passive"))
      (node (ref "*led248") (pin "2") (pinfunction "2_2") (pintype "passive"))
      (node (ref "*led256") (pin "2") (pinfunction "2_2") (pintype "passive"))
      (node (ref "max4") (pin "17") (pinfunction "SEGG_17") (pintype "passive"))
    )
    (net (code "51") (name "/clk11") (class "Default")
      (node (ref "esp32S3") (pin "10") (pinfunction "gpio17_10") (pintype "passive"))
      (node (ref "max1") (pin "13") (pinfunction "CLK_13") (pintype "passive"))
      (node (ref "max2") (pin "13") (pinfunction "CLK_13") (pintype "passive"))
      (node (ref "max3") (pin "13") (pinfunction "CLK_13") (pintype "passive"))
      (node (ref "max4") (pin "13") (pinfunction "CLK_13") (pintype "passive"))
    )
    (net (code "52") (name "/cs12") (class "Default")
      (node (ref "esp32S3") (pin "9") (pinfunction "gpio16_9") (pintype "passive"))
      (node (ref "max1") (pin "12") (pinfunction "LOAD_12") (pintype "passive"))
      (node (ref "max2") (pin "12") (pinfunction "LOAD_12") (pintype "passive"))
      (node (ref "max3") (pin "12") (pinfunction "LOAD_12") (pintype "passive"))
      (node (ref "max4") (pin "12") (pinfunction "LOAD_12") (pintype "passive"))
    )
    (net (code "53") (name "/din13") (class "Default")
      (node (ref "esp32S3") (pin "8") (pinfunction "gpio15_8") (pintype "passive"))
      (node (ref "max1") (pin "1") (pinfunction "DIN_1") (pintype "passive"))
    )
    (net (code "54") (name "/e0") (class "Default")
      (node (ref "ALPS EC1") (pin "B1") (pinfunction "B1_B1") (pintype "passive"))
      (node (ref "mcp1") (pin "21") (pinfunction "GPA0_21") (pintype "passive"))
      (node (ref "r8") (pin "1") (pinfunction "1_1") (pintype "passive"))
    )
    (net (code "55") (name "/e1") (class "Default")
      (node (ref "ALPS EC1") (pin "A1") (pinfunction "A1_A1") (pintype "passive"))
      (node (ref "mcp1") (pin "22") (pinfunction "GPA1_22") (pintype "passive"))
      (node (ref "r9") (pin "1") (pinfunction "1_1") (pintype "passive"))
    )
    (net (code "56") (name "/e2") (class "Default")
      (node (ref "ALPS EC2") (pin "B1") (pinfunction "B1_B1") (pintype "passive"))
      (node (ref "mcp1") (pin "23") (pinfunction "GPA2_23") (pintype "passive"))
      (node (ref "r12") (pin "1") (pinfunction "1_1") (pintype "passive"))
    )
    (net (code "57") (name "/e3") (class "Default")
      (node (ref "ALPS EC2") (pin "A1") (pinfunction "A1_A1") (pintype "passive"))
      (node (ref "mcp1") (pin "24") (pinfunction "GPA3_24") (pintype "passive"))
      (node (ref "r13") (pin "1") (pinfunction "1_1") (pintype "passive"))
    )
    (net (code "58") (name "/e4") (class "Default")
      (node (ref "ALPS EC3") (pin "B1") (pinfunction "B1_B1") (pintype "passive"))
      (node (ref "mcp1") (pin "25") (pinfunction "GPA4_25") (pintype "passive"))
      (node (ref "r16") (pin "1") (pinfunction "1_1") (pintype "passive"))
    )
    (net (code "59") (name "/e5") (class "Default")
      (node (ref "ALPS EC3") (pin "A1") (pinfunction "A1_A1") (pintype "passive"))
      (node (ref "mcp1") (pin "26") (pinfunction "GPA5_26") (pintype "passive"))
      (node (ref "r17") (pin "1") (pinfunction "1_1") (pintype "passive"))
    )
    (net (code "60") (name "/e6") (class "Default")
      (node (ref "ALPS EC4") (pin "B1") (pinfunction "B1_B1") (pintype "passive"))
      (node (ref "mcp1") (pin "27") (pinfunction "GPA6_27") (pintype "passive"))
      (node (ref "r20") (pin "1") (pinfunction "1_1") (pintype "passive"))
    )
    (net (code "61") (name "/e7") (class "Default")
      (node (ref "ALPS EC4") (pin "A1") (pinfunction "A1_A1") (pintype "passive"))
      (node (ref "mcp1") (pin "28") (pinfunction "GPA7_28") (pintype "passive"))
      (node (ref "r21") (pin "1") (pinfunction "1_1") (pintype "passive"))
    )
    (net (code "62") (name "/e8") (class "Default")
      (node (ref "ALPS EC5") (pin "B1") (pinfunction "B1_B1") (pintype "passive"))
      (node (ref "mcp1") (pin "1") (pinfunction "GPB0_1") (pintype "passive"))
      (node (ref "r24") (pin "1") (pinfunction "1_1") (pintype "passive"))
    )
    (net (code "63") (name "/e9") (class "Default")
      (node (ref "ALPS EC5") (pin "A1") (pinfunction "A1_A1") (pintype "passive"))
      (node (ref "mcp1") (pin "2") (pinfunction "GPB1_2") (pintype "passive"))
      (node (ref "r25") (pin "1") (pinfunction "1_1") (pintype "passive"))
    )
    (net (code "64") (name "/e10") (class "Default")
      (node (ref "ALPS EC6") (pin "B1") (pinfunction "B1_B1") (pintype "passive"))
      (node (ref "mcp1") (pin "3") (pinfunction "GPB2_3") (pintype "passive"))
      (node (ref "r28") (pin "1") (pinfunction "1_1") (pintype "passive"))
    )
    (net (code "65") (name "/e11") (class "Default")
      (node (ref "ALPS EC6") (pin "A1") (pinfunction "A1_A1") (pintype "passive"))
      (node (ref "mcp1") (pin "4") (pinfunction "GPB3_4") (pintype "passive"))
      (node (ref "r29") (pin "1") (pinfunction "1_1") (pintype "passive"))
    )
    (net (code "66") (name "/e12") (class "Default")
      (node (ref "ALPS EC7") (pin "B1") (pinfunction "B1_B1") (pintype "passive"))
      (node (ref "mcp1") (pin "5") (pinfunction "GPB4_5") (pintype "passive"))
      (node (ref "r32") (pin "1") (pinfunction "1_1") (pintype "passive"))
    )
    (net (code "67") (name "/e13") (class "Default")
      (node (ref "ALPS EC7") (pin "A1") (pinfunction "A1_A1") (pintype "passive"))
      (node (ref "mcp1") (pin "6") (pinfunction "GPB5_6") (pintype "passive"))
      (node (ref "r33") (pin "1") (pinfunction "1_1") (pintype "passive"))
    )
    (net (code "68") (name "/e14") (class "Default")
      (node (ref "ALPS EC8") (pin "B1") (pinfunction "B1_B1") (pintype "passive"))
      (node (ref "mcp1") (pin "7") (pinfunction "GPB6_7") (pintype "passive"))
      (node (ref "r36") (pin "1") (pinfunction "1_1") (pintype "passive"))
    )
    (net (code "69") (name "/e15") (class "Default")
      (node (ref "ALPS EC8") (pin "A1") (pinfunction "A1_A1") (pintype "passive"))
      (node (ref "mcp1") (pin "8") (pinfunction "GPB7_8") (pintype "passive"))
      (node (ref "r37") (pin "1") (pinfunction "1_1") (pintype "passive"))
    )
    (net (code "70") (name "/e16") (class "Default")
      (node (ref "ALPS EC9") (pin "B1") (pinfunction "B1_B1") (pintype "passive"))
      (node (ref "mcp2") (pin "21") (pinfunction "GPA0_21") (pintype "passive"))
      (node (ref "r10") (pin "1") (pinfunction "1_1") (pintype "passive"))
    )
    (net (code "71") (name "/e17") (class "Default")
      (node (ref "ALPS EC9") (pin "A1") (pinfunction "A1_A1") (pintype "passive"))
      (node (ref "mcp2") (pin "22") (pinfunction "GPA1_22") (pintype "passive"))
      (node (ref "r11") (pin "1") (pinfunction "1_1") (pintype "passive"))
    )
    (net (code "72") (name "/e18") (class "Default")
      (node (ref "ALPS EC10") (pin "B1") (pinfunction "B1_B1") (pintype "passive"))
      (node (ref "mcp2") (pin "23") (pinfunction "GPA2_23") (pintype "passive"))
      (node (ref "r14") (pin "1") (pinfunction "1_1") (pintype "passive"))
    )
    (net (code "73") (name "/e19") (class "Default")
      (node (ref "ALPS EC10") (pin "A1") (pinfunction "A1_A1") (pintype "passive"))
      (node (ref "mcp2") (pin "24") (pinfunction "GPA3_24") (pintype "passive"))
      (node (ref "r15") (pin "1") (pinfunction "1_1") (pintype "passive"))
    )
    (net (code "74") (name "/e20") (class "Default")
      (node (ref "ALPS EC11") (pin "B1") (pinfunction "B1_B1") (pintype "passive"))
      (node (ref "mcp2") (pin "25") (pinfunction "GPA4_25") (pintype "passive"))
      (node (ref "r18") (pin "1") (pinfunction "1_1") (pintype "passive"))
    )
    (net (code "75") (name "/e21") (class "Default")
      (node (ref "ALPS EC11") (pin "A1") (pinfunction "A1_A1") (pintype "passive"))
      (node (ref "mcp2") (pin "26") (pinfunction "GPA5_26") (pintype "passive"))
      (node (ref "r19") (pin "1") (pinfunction "1_1") (pintype "passive"))
    )
    (net (code "76") (name "/e22") (class "Default")
      (node (ref "ALPS EC12") (pin "B1") (pinfunction "B1_B1") (pintype "passive"))
      (node (ref "mcp2") (pin "27") (pinfunction "GPA6_27") (pintype "passive"))
      (node (ref "r22") (pin "1") (pinfunction "1_1") (pintype "passive"))
    )
    (net (code "77") (name "/e23") (class "Default")
      (node (ref "ALPS EC12") (pin "A1") (pinfunction "A1_A1") (pintype "passive"))
      (node (ref "mcp2") (pin "28") (pinfunction "GPA7_28") (pintype "passive"))
      (node (ref "r23") (pin "1") (pinfunction "1_1") (pintype "passive"))
    )
    (net (code "78") (name "/e24") (class "Default")
      (node (ref "ALPS EC13") (pin "B1") (pinfunction "B1_B1") (pintype "passive"))
      (node (ref "mcp2") (pin "1") (pinfunction "GPB0_1") (pintype "passive"))
      (node (ref "r26") (pin "1") (pinfunction "1_1") (pintype "passive"))
    )
    (net (code "79") (name "/e25") (class "Default")
      (node (ref "ALPS EC13") (pin "A1") (pinfunction "A1_A1") (pintype "passive"))
      (node (ref "mcp2") (pin "2") (pinfunction "GPB1_2") (pintype "passive"))
      (node (ref "r27") (pin "1") (pinfunction "1_1") (pintype "passive"))
    )
    (net (code "80") (name "/e26") (class "Default")
      (node (ref "ALPS EC14") (pin "B1") (pinfunction "B1_B1") (pintype "passive"))
      (node (ref "mcp2") (pin "3") (pinfunction "GPB2_3") (pintype "passive"))
      (node (ref "r30") (pin "1") (pinfunction "1_1") (pintype "passive"))
    )
    (net (code "81") (name "/e27") (class "Default")
      (node (ref "ALPS EC14") (pin "A1") (pinfunction "A1_A1") (pintype "passive"))
      (node (ref "mcp2") (pin "4") (pinfunction "GPB3_4") (pintype "passive"))
      (node (ref "r31") (pin "1") (pinfunction "1_1") (pintype "passive"))
    )
    (net (code "82") (name "/e28") (class "Default")
      (node (ref "ALPS EC15") (pin "B1") (pinfunction "B1_B1") (pintype "passive"))
      (node (ref "mcp2") (pin "5") (pinfunction "GPB4_5") (pintype "passive"))
      (node (ref "r34") (pin "1") (pinfunction "1_1") (pintype "passive"))
    )
    (net (code "83") (name "/e29") (class "Default")
      (node (ref "ALPS EC15") (pin "A1") (pinfunction "A1_A1") (pintype "passive"))
      (node (ref "mcp2") (pin "6") (pinfunction "GPB5_6") (pintype "passive"))
      (node (ref "r35") (pin "1") (pinfunction "1_1") (pintype "passive"))
    )
    (net (code "84") (name "/e30") (class "Default")
      (node (ref "ALPS EC16") (pin "B1") (pinfunction "B1_B1") (pintype "passive"))
      (node (ref "mcp2") (pin "7") (pinfunction "GPB6_7") (pintype "passive"))
      (node (ref "r38") (pin "1") (pinfunction "1_1") (pintype "passive"))
    )
    (net (code "85") (name "/e31") (class "Default")
      (node (ref "ALPS EC16") (pin "A1") (pinfunction "A1_A1") (pintype "passive"))
      (node (ref "mcp2") (pin "8") (pinfunction "GPB7_8") (pintype "passive"))
      (node (ref "r39") (pin "1") (pinfunction "1_1") (pintype "passive"))
    )
    (net (code "86") (name "/r1_1") (class "Default")
      (node (ref "*led1") (pin "1") (pinfunction "1_1") (pintype "passive"))
      (node (ref "*led2") (pin "1") (pinfunction "1_1") (pintype "passive"))
      (node (ref "*led3") (pin "1") (pinfunction "1_1") (pintype "passive"))
      (node (ref "*led4") (pin "1") (pinfunction "1_1") (pintype "passive"))
      (node (ref "*led5") (pin "1") (pinfunction "1_1") (pintype "passive"))
      (node (ref "*led6") (pin "1") (pinfunction "1_1") (pintype "passive"))
      (node (ref "*led7") (pin "1") (pinfunction "1_1") (pintype "passive"))
      (node (ref "*led8") (pin "1") (pinfunction "1_1") (pintype "passive"))
      (node (ref "max1") (pin "2") (pinfunction "DIG0_2") (pintype "passive"))
    )
    (net (code "87") (name "/r1_2") (class "Default")
      (node (ref "*led10") (pin "1") (pinfunction "1_1") (pintype "passive"))
      (node (ref "*led11") (pin "1") (pinfunction "1_1") (pintype "passive"))
      (node (ref "*led12") (pin "1") (pinfunction "1_1") (pintype "passive"))
      (node (ref "*led13") (pin "1") (pinfunction "1_1") (pintype "passive"))
      (node (ref "*led14") (pin "1") (pinfunction "1_1") (pintype "passive"))
      (node (ref "*led15") (pin "1") (pinfunction "1_1") (pintype "passive"))
      (node (ref "*led16") (pin "1") (pinfunction "1_1") (pintype "passive"))
      (node (ref "*led9") (pin "1") (pinfunction "1_1") (pintype "passive"))
      (node (ref "max1") (pin "11") (pinfunction "DIG1_11") (pintype "passive"))
    )
    (net (code "88") (name "/r1_3") (class "Default")
      (node (ref "*led17") (pin "1") (pinfunction "1_1") (pintype "passive"))
      (node (ref "*led18") (pin "1") (pinfunction "1_1") (pintype "passive"))
      (node (ref "*led19") (pin "1") (pinfunction "1_1") (pintype "passive"))
      (node (ref "*led20") (pin "1") (pinfunction "1_1") (pintype "passive"))
      (node (ref "*led21") (pin "1") (pinfunction "1_1") (pintype "passive"))
      (node (ref "*led22") (pin "1") (pinfunction "1_1") (pintype "passive"))
      (node (ref "*led23") (pin "1") (pinfunction "1_1") (pintype "passive"))
      (node (ref "*led24") (pin "1") (pinfunction "1_1") (pintype "passive"))
      (node (ref "max1") (pin "6") (pinfunction "DIG2_6") (pintype "passive"))
    )
    (net (code "89") (name "/r1_4") (class "Default")
      (node (ref "*led25") (pin "1") (pinfunction "1_1") (pintype "passive"))
      (node (ref "*led26") (pin "1") (pinfunction "1_1") (pintype "passive"))
      (node (ref "*led27") (pin "1") (pinfunction "1_1") (pintype "passive"))
      (node (ref "*led28") (pin "1") (pinfunction "1_1") (pintype "passive"))
      (node (ref "*led29") (pin "1") (pinfunction "1_1") (pintype "passive"))
      (node (ref "*led30") (pin "1") (pinfunction "1_1") (pintype "passive"))
      (node (ref "*led31") (pin "1") (pinfunction "1_1") (pintype "passive"))
      (node (ref "*led32") (pin "1") (pinfunction "1_1") (pintype "passive"))
      (node (ref "max1") (pin "7") (pinfunction "DIG3_7") (pintype "passive"))
    )
    (net (code "90") (name "/r1_5") (class "Default")
      (node (ref "*led33") (pin "1") (pinfunction "1_1") (pintype "passive"))
      (node (ref "*led34") (pin "1") (pinfunction "1_1") (pintype "passive"))
      (node (ref "*led35") (pin "1") (pinfunction "1_1") (pintype "passive"))
      (node (ref "*led36") (pin "1") (pinfunction "1_1") (pintype "passive"))
      (node (ref "*led37") (pin "1") (pinfunction "1_1") (pintype "passive"))
      (node (ref "*led38") (pin "1") (pinfunction "1_1") (pintype "passive"))
      (node (ref "*led39") (pin "1") (pinfunction "1_1") (pintype "passive"))
      (node (ref "*led40") (pin "1") (pinfunction "1_1") (pintype "passive"))
      (node (ref "max1") (pin "3") (pinfunction "DIG4_3") (pintype "passive"))
    )
    (net (code "91") (name "/r1_6") (class "Default")
      (node (ref "*led41") (pin "1") (pinfunction "1_1") (pintype "passive"))
      (node (ref "*led42") (pin "1") (pinfunction "1_1") (pintype "passive"))
      (node (ref "*led43") (pin "1") (pinfunction "1_1") (pintype "passive"))
      (node (ref "*led44") (pin "1") (pinfunction "1_1") (pintype "passive"))
      (node (ref "*led45") (pin "1") (pinfunction "1_1") (pintype "passive"))
      (node (ref "*led46") (pin "1") (pinfunction "1_1") (pintype "passive"))
      (node (ref "*led47") (pin "1") (pinfunction "1_1") (pintype "passive"))
      (node (ref "*led48") (pin "1") (pinfunction "1_1") (pintype "passive"))
      (node (ref "max1") (pin "10") (pinfunction "DIG5_10") (pintype "passive"))
    )
    (net (code "92") (name "/r1_7") (class "Default")
      (node (ref "*led49") (pin "1") (pinfunction "1_1") (pintype "passive"))
      (node (ref "*led50") (pin "1") (pinfunction "1_1") (pintype "passive"))
      (node (ref "*led51") (pin "1") (pinfunction "1_1") (pintype "passive"))
      (node (ref "*led52") (pin "1") (pinfunction "1_1") (pintype "passive"))
      (node (ref "*led53") (pin "1") (pinfunction "1_1") (pintype "passive"))
      (node (ref "*led54") (pin "1") (pinfunction "1_1") (pintype "passive"))
      (node (ref "*led55") (pin "1") (pinfunction "1_1") (pintype "passive"))
      (node (ref "*led56") (pin "1") (pinfunction "1_1") (pintype "passive"))
      (node (ref "max1") (pin "5") (pinfunction "DIG6_5") (pintype "passive"))
    )
    (net (code "93") (name "/r1_8") (class "Default")
      (node (ref "*led57") (pin "1") (pinfunction "1_1") (pintype "passive"))
      (node (ref "*led58") (pin "1") (pinfunction "1_1") (pintype "passive"))
      (node (ref "*led59") (pin "1") (pinfunction "1_1") (pintype "passive"))
      (node (ref "*led60") (pin "1") (pinfunction "1_1") (pintype "passive"))
      (node (ref "*led61") (pin "1") (pinfunction "1_1") (pintype "passive"))
      (node (ref "*led62") (pin "1") (pinfunction "1_1") (pintype "passive"))
      (node (ref "*led63") (pin "1") (pinfunction "1_1") (pintype "passive"))
      (node (ref "*led64") (pin "1") (pinfunction "1_1") (pintype "passive"))
      (node (ref "max1") (pin "8") (pinfunction "DIG7_8") (pintype "passive"))
    )
    (net (code "94") (name "/r2_1") (class "Default")
      (node (ref "*led65") (pin "1") (pinfunction "1_1") (pintype "passive"))
      (node (ref "*led66") (pin "1") (pinfunction "1_1") (pintype "passive"))
      (node (ref "*led67") (pin "1") (pinfunction "1_1") (pintype "passive"))
      (node (ref "*led68") (pin "1") (pinfunction "1_1") (pintype "passive"))
      (node (ref "*led69") (pin "1") (pinfunction "1_1") (pintype "passive"))
      (node (ref "*led70") (pin "1") (pinfunction "1_1") (pintype "passive"))
      (node (ref "*led71") (pin "1") (pinfunction "1_1") (pintype "passive"))
      (node (ref "*led72") (pin "1") (pinfunction "1_1") (pintype "passive"))
      (node (ref "max2") (pin "2") (pinfunction "DIG0_2") (pintype "passive"))
    )
    (net (code "95") (name "/r2_2") (class "Default")
      (node (ref "*led73") (pin "1") (pinfunction "1_1") (pintype "passive"))
      (node (ref "*led74") (pin "1") (pinfunction "1_1") (pintype "passive"))
      (node (ref "*led75") (pin "1") (pinfunction "1_1") (pintype "passive"))
      (node (ref "*led76") (pin "1") (pinfunction "1_1") (pintype "passive"))
      (node (ref "*led77") (pin "1") (pinfunction "1_1") (pintype "passive"))
      (node (ref "*led78") (pin "1") (pinfunction "1_1") (pintype "passive"))
      (node (ref "*led79") (pin "1") (pinfunction "1_1") (pintype "passive"))
      (node (ref "*led80") (pin "1") (pinfunction "1_1") (pintype "passive"))
      (node (ref "max2") (pin "11") (pinfunction "DIG1_11") (pintype "passive"))
    )
    (net (code "96") (name "/r2_3") (class "Default")
      (node (ref "*led81") (pin "1") (pinfunction "1_1") (pintype "passive"))
      (node (ref "*led82") (pin "1") (pinfunction "1_1") (pintype "passive"))
      (node (ref "*led83") (pin "1") (pinfunction "1_1") (pintype "passive"))
      (node (ref "*led84") (pin "1") (pinfunction "1_1") (pintype "passive"))
      (node (ref "*led85") (pin "1") (pinfunction "1_1") (pintype "passive"))
      (node (ref "*led86") (pin "1") (pinfunction "1_1") (pintype "passive"))
      (node (ref "*led87") (pin "1") (pinfunction "1_1") (pintype "passive"))
      (node (ref "*led88") (pin "1") (pinfunction "1_1") (pintype "passive"))
      (node (ref "max2") (pin "6") (pinfunction "DIG2_6") (pintype "passive"))
    )
    (net (code "97") (name "/r2_4") (class "Default")
      (node (ref "*led89") (pin "1") (pinfunction "1_1") (pintype "passive"))
      (node (ref "*led90") (pin "1") (pinfunction "1_1") (pintype "passive"))
      (node (ref "*led91") (pin "1") (pinfunction "1_1") (pintype "passive"))
      (node (ref "*led92") (pin "1") (pinfunction "1_1") (pintype "passive"))
      (node (ref "*led93") (pin "1") (pinfunction "1_1") (pintype "passive"))
      (node (ref "*led94") (pin "1") (pinfunction "1_1") (pintype "passive"))
      (node (ref "*led95") (pin "1") (pinfunction "1_1") (pintype "passive"))
      (node (ref "*led96") (pin "1") (pinfunction "1_1") (pintype "passive"))
      (node (ref "max2") (pin "7") (pinfunction "DIG3_7") (pintype "passive"))
    )
    (net (code "98") (name "/r2_5") (class "Default")
      (node (ref "*led100") (pin "1") (pinfunction "1_1") (pintype "passive"))
      (node (ref "*led101") (pin "1") (pinfunction "1_1") (pintype "passive"))
      (node (ref "*led102") (pin "1") (pinfunction "1_1") (pintype "passive"))
      (node (ref "*led103") (pin "1") (pinfunction "1_1") (pintype "passive"))
      (node (ref "*led104") (pin "1") (pinfunction "1_1") (pintype "passive"))
      (node (ref "*led97") (pin "1") (pinfunction "1_1") (pintype "passive"))
      (node (ref "*led98") (pin "1") (pinfunction "1_1") (pintype "passive"))
      (node (ref "*led99") (pin "1") (pinfunction "1_1") (pintype "passive"))
      (node (ref "max2") (pin "3") (pinfunction "DIG4_3") (pintype "passive"))
    )
    (net (code "99") (name "/r2_6") (class "Default")
      (node (ref "*led105") (pin "1") (pinfunction "1_1") (pintype "passive"))
      (node (ref "*led106") (pin "1") (pinfunction "1_1") (pintype "passive"))
      (node (ref "*led107") (pin "1") (pinfunction "1_1") (pintype "passive"))
      (node (ref "*led108") (pin "1") (pinfunction "1_1") (pintype "passive"))
      (node (ref "*led109") (pin "1") (pinfunction "1_1") (pintype "passive"))
      (node (ref "*led110") (pin "1") (pinfunction "1_1") (pintype "passive"))
      (node (ref "*led111") (pin "1") (pinfunction "1_1") (pintype "passive"))
      (node (ref "*led112") (pin "1") (pinfunction "1_1") (pintype "passive"))
      (node (ref "max2") (pin "10") (pinfunction "DIG5_10") (pintype "passive"))
    )
    (net (code "100") (name "/r2_7") (class "Default")
      (node (ref "*led113") (pin "1") (pinfunction "1_1") (pintype "passive"))
      (node (ref "*led114") (pin "1") (pinfunction "1_1") (pintype "passive"))
      (node (ref "*led115") (pin "1") (pinfunction "1_1") (pintype "passive"))
      (node (ref "*led116") (pin "1") (pinfunction "1_1") (pintype "passive"))
      (node (ref "*led117") (pin "1") (pinfunction "1_1") (pintype "passive"))
      (node (ref "*led118") (pin "1") (pinfunction "1_1") (pintype "passive"))
      (node (ref "*led119") (pin "1") (pinfunction "1_1") (pintype "passive"))
      (node (ref "*led120") (pin "1") (pinfunction "1_1") (pintype "passive"))
      (node (ref "max2") (pin "5") (pinfunction "DIG6_5") (pintype "passive"))
    )
    (net (code "101") (name "/r2_8") (class "Default")
      (node (ref "*led121") (pin "1") (pinfunction "1_1") (pintype "passive"))
      (node (ref "*led122") (pin "1") (pinfunction "1_1") (pintype "passive"))
      (node (ref "*led123") (pin "1") (pinfunction "1_1") (pintype "passive"))
      (node (ref "*led124") (pin "1") (pinfunction "1_1") (pintype "passive"))
      (node (ref "*led125") (pin "1") (pinfunction "1_1") (pintype "passive"))
      (node (ref "*led126") (pin "1") (pinfunction "1_1") (pintype "passive"))
      (node (ref "*led127") (pin "1") (pinfunction "1_1") (pintype "passive"))
      (node (ref "*led128") (pin "1") (pinfunction "1_1") (pintype "passive"))
      (node (ref "max2") (pin "8") (pinfunction "DIG7_8") (pintype "passive"))
    )
    (net (code "102") (name "/r3_1") (class "Default")
      (node (ref "*led129") (pin "1") (pinfunction "1_1") (pintype "passive"))
      (node (ref "*led130") (pin "1") (pinfunction "1_1") (pintype "passive"))
      (node (ref "*led131") (pin "1") (pinfunction "1_1") (pintype "passive"))
      (node (ref "*led132") (pin "1") (pinfunction "1_1") (pintype "passive"))
      (node (ref "*led133") (pin "1") (pinfunction "1_1") (pintype "passive"))
      (node (ref "*led134") (pin "1") (pinfunction "1_1") (pintype "passive"))
      (node (ref "*led135") (pin "1") (pinfunction "1_1") (pintype "passive"))
      (node (ref "*led136") (pin "1") (pinfunction "1_1") (pintype "passive"))
      (node (ref "max3") (pin "2") (pinfunction "DIG0_2") (pintype "passive"))
    )
    (net (code "103") (name "/r3_2") (class "Default")
      (node (ref "*led137") (pin "1") (pinfunction "1_1") (pintype "passive"))
      (node (ref "*led138") (pin "1") (pinfunction "1_1") (pintype "passive"))
      (node (ref "*led139") (pin "1") (pinfunction "1_1") (pintype "passive"))
      (node (ref "*led140") (pin "1") (pinfunction "1_1") (pintype "passive"))
      (node (ref "*led141") (pin "1") (pinfunction "1_1") (pintype "passive"))
      (node (ref "*led142") (pin "1") (pinfunction "1_1") (pintype "passive"))
      (node (ref "*led143") (pin "1") (pinfunction "1_1") (pintype "passive"))
      (node (ref "*led144") (pin "1") (pinfunction "1_1") (pintype "passive"))
      (node (ref "max3") (pin "11") (pinfunction "DIG1_11") (pintype "passive"))
    )
    (net (code "104") (name "/r3_3") (class "Default")
      (node (ref "*led145") (pin "1") (pinfunction "1_1") (pintype "passive"))
      (node (ref "*led146") (pin "1") (pinfunction "1_1") (pintype "passive"))
      (node (ref "*led147") (pin "1") (pinfunction "1_1") (pintype "passive"))
      (node (ref "*led148") (pin "1") (pinfunction "1_1") (pintype "passive"))
      (node (ref "*led149") (pin "1") (pinfunction "1_1") (pintype "passive"))
      (node (ref "*led150") (pin "1") (pinfunction "1_1") (pintype "passive"))
      (node (ref "*led151") (pin "1") (pinfunction "1_1") (pintype "passive"))
      (node (ref "*led152") (pin "1") (pinfunction "1_1") (pintype "passive"))
      (node (ref "max3") (pin "6") (pinfunction "DIG2_6") (pintype "passive"))
    )
    (net (code "105") (name "/r3_4") (class "Default")
      (node (ref "*led153") (pin "1") (pinfunction "1_1") (pintype "passive"))
      (node (ref "*led154") (pin "1") (pinfunction "1_1") (pintype "passive"))
      (node (ref "*led155") (pin "1") (pinfunction "1_1") (pintype "passive"))
      (node (ref "*led156") (pin "1") (pinfunction "1_1") (pintype "passive"))
      (node (ref "*led157") (pin "1") (pinfunction "1_1") (pintype "passive"))
      (node (ref "*led158") (pin "1") (pinfunction "1_1") (pintype "passive"))
      (node (ref "*led159") (pin "1") (pinfunction "1_1") (pintype "passive"))
      (node (ref "*led160") (pin "1") (pinfunction "1_1") (pintype "passive"))
      (node (ref "max3") (pin "7") (pinfunction "DIG3_7") (pintype "passive"))
    )
    (net (code "106") (name "/r3_5") (class "Default")
      (node (ref "*led161") (pin "1") (pinfunction "1_1") (pintype "passive"))
      (node (ref "*led162") (pin "1") (pinfunction "1_1") (pintype "passive"))
      (node (ref "*led163") (pin "1") (pinfunction "1_1") (pintype "passive"))
      (node (ref "*led164") (pin "1") (pinfunction "1_1") (pintype "passive"))
      (node (ref "*led165") (pin "1") (pinfunction "1_1") (pintype "passive"))
      (node (ref "*led166") (pin "1") (pinfunction "1_1") (pintype "passive"))
      (node (ref "*led167") (pin "1") (pinfunction "1_1") (pintype "passive"))
      (node (ref "*led168") (pin "1") (pinfunction "1_1") (pintype "passive"))
      (node (ref "max3") (pin "3") (pinfunction "DIG4_3") (pintype "passive"))
    )
    (net (code "107") (name "/r3_6") (class "Default")
      (node (ref "*led169") (pin "1") (pinfunction "1_1") (pintype "passive"))
      (node (ref "*led170") (pin "1") (pinfunction "1_1") (pintype "passive"))
      (node (ref "*led171") (pin "1") (pinfunction "1_1") (pintype "passive"))
      (node (ref "*led172") (pin "1") (pinfunction "1_1") (pintype "passive"))
      (node (ref "*led173") (pin "1") (pinfunction "1_1") (pintype "passive"))
      (node (ref "*led174") (pin "1") (pinfunction "1_1") (pintype "passive"))
      (node (ref "*led175") (pin "1") (pinfunction "1_1") (pintype "passive"))
      (node (ref "*led176") (pin "1") (pinfunction "1_1") (pintype "passive"))
      (node (ref "max3") (pin "10") (pinfunction "DIG5_10") (pintype "passive"))
    )
    (net (code "108") (name "/r3_7") (class "Default")
      (node (ref "*led177") (pin "1") (pinfunction "1_1") (pintype "passive"))
      (node (ref "*led178") (pin "1") (pinfunction "1_1") (pintype "passive"))
      (node (ref "*led179") (pin "1") (pinfunction "1_1") (pintype "passive"))
      (node (ref "*led180") (pin "1") (pinfunction "1_1") (pintype "passive"))
      (node (ref "*led181") (pin "1") (pinfunction "1_1") (pintype "passive"))
      (node (ref "*led182") (pin "1") (pinfunction "1_1") (pintype "passive"))
      (node (ref "*led183") (pin "1") (pinfunction "1_1") (pintype "passive"))
      (node (ref "*led184") (pin "1") (pinfunction "1_1") (pintype "passive"))
      (node (ref "max3") (pin "5") (pinfunction "DIG6_5") (pintype "passive"))
    )
    (net (code "109") (name "/r3_8") (class "Default")
      (node (ref "*led185") (pin "1") (pinfunction "1_1") (pintype "passive"))
      (node (ref "*led186") (pin "1") (pinfunction "1_1") (pintype "passive"))
      (node (ref "*led187") (pin "1") (pinfunction "1_1") (pintype "passive"))
      (node (ref "*led188") (pin "1") (pinfunction "1_1") (pintype "passive"))
      (node (ref "*led189") (pin "1") (pinfunction "1_1") (pintype "passive"))
      (node (ref "*led190") (pin "1") (pinfunction "1_1") (pintype "passive"))
      (node (ref "*led191") (pin "1") (pinfunction "1_1") (pintype "passive"))
      (node (ref "*led192") (pin "1") (pinfunction "1_1") (pintype "passive"))
      (node (ref "max3") (pin "8") (pinfunction "DIG7_8") (pintype "passive"))
    )
    (net (code "110") (name "/r4_1") (class "Default")
      (node (ref "*led193") (pin "1") (pinfunction "1_1") (pintype "passive"))
      (node (ref "*led194") (pin "1") (pinfunction "1_1") (pintype "passive"))
      (node (ref "*led195") (pin "1") (pinfunction "1_1") (pintype "passive"))
      (node (ref "*led196") (pin "1") (pinfunction "1_1") (pintype "passive"))
      (node (ref "*led197") (pin "1") (pinfunction "1_1") (pintype "passive"))
      (node (ref "*led198") (pin "1") (pinfunction "1_1") (pintype "passive"))
      (node (ref "*led199") (pin "1") (pinfunction "1_1") (pintype "passive"))
      (node (ref "*led200") (pin "1") (pinfunction "1_1") (pintype "passive"))
      (node (ref "max4") (pin "2") (pinfunction "DIG0_2") (pintype "passive"))
    )
    (net (code "111") (name "/r4_2") (class "Default")
      (node (ref "*led201") (pin "1") (pinfunction "1_1") (pintype "passive"))
      (node (ref "*led202") (pin "1") (pinfunction "1_1") (pintype "passive"))
      (node (ref "*led203") (pin "1") (pinfunction "1_1") (pintype "passive"))
      (node (ref "*led204") (pin "1") (pinfunction "1_1") (pintype "passive"))
      (node (ref "*led205") (pin "1") (pinfunction "1_1") (pintype "passive"))
      (node (ref "*led206") (pin "1") (pinfunction "1_1") (pintype "passive"))
      (node (ref "*led207") (pin "1") (pinfunction "1_1") (pintype "passive"))
      (node (ref "*led208") (pin "1") (pinfunction "1_1") (pintype "passive"))
      (node (ref "max4") (pin "11") (pinfunction "DIG1_11") (pintype "passive"))
    )
    (net (code "112") (name "/r4_3") (class "Default")
      (node (ref "*led209") (pin "1") (pinfunction "1_1") (pintype "passive"))
      (node (ref "*led210") (pin "1") (pinfunction "1_1") (pintype "passive"))
      (node (ref "*led211") (pin "1") (pinfunction "1_1") (pintype "passive"))
      (node (ref "*led212") (pin "1") (pinfunction "1_1") (pintype "passive"))
      (node (ref "*led213") (pin "1") (pinfunction "1_1") (pintype "passive"))
      (node (ref "*led214") (pin "1") (pinfunction "1_1") (pintype "passive"))
      (node (ref "*led215") (pin "1") (pinfunction "1_1") (pintype "passive"))
      (node (ref "*led216") (pin "1") (pinfunction "1_1") (pintype "passive"))
      (node (ref "max4") (pin "6") (pinfunction "DIG2_6") (pintype "passive"))
    )
    (net (code "113") (name "/r4_4") (class "Default")
      (node (ref "*led217") (pin "1") (pinfunction "1_1") (pintype "passive"))
      (node (ref "*led218") (pin "1") (pinfunction "1_1") (pintype "passive"))
      (node (ref "*led219") (pin "1") (pinfunction "1_1") (pintype "passive"))
      (node (ref "*led220") (pin "1") (pinfunction "1_1") (pintype "passive"))
      (node (ref "*led221") (pin "1") (pinfunction "1_1") (pintype "passive"))
      (node (ref "*led222") (pin "1") (pinfunction "1_1") (pintype "passive"))
      (node (ref "*led223") (pin "1") (pinfunction "1_1") (pintype "passive"))
      (node (ref "*led224") (pin "1") (pinfunction "1_1") (pintype "passive"))
      (node (ref "max4") (pin "7") (pinfunction "DIG3_7") (pintype "passive"))
    )
    (net (code "114") (name "/r4_5") (class "Default")
      (node (ref "*led225") (pin "1") (pinfunction "1_1") (pintype "passive"))
      (node (ref "*led226") (pin "1") (pinfunction "1_1") (pintype "passive"))
      (node (ref "*led227") (pin "1") (pinfunction "1_1") (pintype "passive"))
      (node (ref "*led228") (pin "1") (pinfunction "1_1") (pintype "passive"))
      (node (ref "*led229") (pin "1") (pinfunction "1_1") (pintype "passive"))
      (node (ref "*led230") (pin "1") (pinfunction "1_1") (pintype "passive"))
      (node (ref "*led231") (pin "1") (pinfunction "1_1") (pintype "passive"))
      (node (ref "*led232") (pin "1") (pinfunction "1_1") (pintype "passive"))
      (node (ref "max4") (pin "3") (pinfunction "DIG4_3") (pintype "passive"))
    )
    (net (code "115") (name "/r4_6") (class "Default")
      (node (ref "*led233") (pin "1") (pinfunction "1_1") (pintype "passive"))
      (node (ref "*led234") (pin "1") (pinfunction "1_1") (pintype "passive"))
      (node (ref "*led235") (pin "1") (pinfunction "1_1") (pintype "passive"))
      (node (ref "*led236") (pin "1") (pinfunction "1_1") (pintype "passive"))
      (node (ref "*led237") (pin "1") (pinfunction "1_1") (pintype "passive"))
      (node (ref "*led238") (pin "1") (pinfunction "1_1") (pintype "passive"))
      (node (ref "*led239") (pin "1") (pinfunction "1_1") (pintype "passive"))
      (node (ref "*led240") (pin "1") (pinfunction "1_1") (pintype "passive"))
      (node (ref "max4") (pin "10") (pinfunction "DIG5_10") (pintype "passive"))
    )
    (net (code "116") (name "/r4_7") (class "Default")
      (node (ref "*led241") (pin "1") (pinfunction "1_1") (pintype "passive"))
      (node (ref "*led242") (pin "1") (pinfunction "1_1") (pintype "passive"))
      (node (ref "*led243") (pin "1") (pinfunction "1_1") (pintype "passive"))
      (node (ref "*led244") (pin "1") (pinfunction "1_1") (pintype "passive"))
      (node (ref "*led245") (pin "1") (pinfunction "1_1") (pintype "passive"))
      (node (ref "*led246") (pin "1") (pinfunction "1_1") (pintype "passive"))
      (node (ref "*led247") (pin "1") (pinfunction "1_1") (pintype "passive"))
      (node (ref "*led248") (pin "1") (pinfunction "1_1") (pintype "passive"))
      (node (ref "max4") (pin "5") (pinfunction "DIG6_5") (pintype "passive"))
    )
    (net (code "117") (name "/r4_8") (class "Default")
      (node (ref "*led249") (pin "1") (pinfunction "1_1") (pintype "passive"))
      (node (ref "*led250") (pin "1") (pinfunction "1_1") (pintype "passive"))
      (node (ref "*led251") (pin "1") (pinfunction "1_1") (pintype "passive"))
      (node (ref "*led252") (pin "1") (pinfunction "1_1") (pintype "passive"))
      (node (ref "*led253") (pin "1") (pinfunction "1_1") (pintype "passive"))
      (node (ref "*led254") (pin "1") (pinfunction "1_1") (pintype "passive"))
      (node (ref "*led255") (pin "1") (pinfunction "1_1") (pintype "passive"))
      (node (ref "*led256") (pin "1") (pinfunction "1_1") (pintype "passive"))
      (node (ref "max4") (pin "8") (pinfunction "DIG7_8") (pintype "passive"))
    )
    (net (code "118") (name "/s0") (class "Default")
      (node (ref "4067") (pin "10") (pinfunction "S0_10") (pintype "passive"))
      (node (ref "esp32S3") (pin "11") (pinfunction "gpio18_11") (pintype "passive"))
    )
    (net (code "119") (name "/s1") (class "Default")
      (node (ref "4067") (pin "11") (pinfunction "S1_11") (pintype "passive"))
      (node (ref "esp32S3") (pin "12") (pinfunction "gpio8_12") (pintype "passive"))
    )
    (net (code "120") (name "/s2") (class "Default")
      (node (ref "4067") (pin "14") (pinfunction "S2_14") (pintype "passive"))
      (node (ref "esp32S3") (pin "31") (pinfunction "gpio38_31") (pintype "passive"))
    )
    (net (code "121") (name "/s3") (class "Default")
      (node (ref "4067") (pin "13") (pinfunction "S3_13") (pintype "passive"))
      (node (ref "esp32S3") (pin "30") (pinfunction "gpio39_30") (pintype "passive"))
    )
    (net (code "122") (name "/scl_encoder") (class "Default")
      (node (ref "esp32S2") (pin "D18") (pinfunction "D18_D18") (pintype "passive"))
      (node (ref "esp32S3") (pin "33") (pinfunction "gpio36_33") (pintype "passive"))
    )
    (net (code "123") (name "/scl_mcp") (class "Default")
      (node (ref "esp32S2") (pin "D22") (pinfunction "D22_D22") (pintype "passive"))
      (node (ref "mcp1") (pin "12") (pinfunction "SCK_12") (pintype "passive"))
      (node (ref "mcp2") (pin "12") (pinfunction "SCK_12") (pintype "passive"))
      (node (ref "r6") (pin "1") (pinfunction "1_1") (pintype "passive"))
    )
    (net (code "124") (name "/sda_encoder") (class "Default")
      (node (ref "esp32S2") (pin "D19") (pinfunction "D19_D19") (pintype "passive"))
      (node (ref "esp32S3") (pin "34") (pinfunction "gpio35_34") (pintype "passive"))
    )
    (net (code "125") (name "/sda_mcp") (class "Default")
      (node (ref "esp32S2") (pin "D21") (pinfunction "D21_D21") (pintype "passive"))
      (node (ref "mcp1") (pin "13") (pinfunction "SDA_13") (pintype "passive"))
      (node (ref "mcp2") (pin "13") (pinfunction "SDA_13") (pintype "passive"))
      (node (ref "r5") (pin "1") (pinfunction "1_1") (pintype "passive"))
    )
    (net (code "126") (name "/z") (class "Default")
      (node (ref "4067") (pin "1") (pinfunction "Z_1") (pintype "passive"))
      (node (ref "esp32S3") (pin "15") (pinfunction "gpio3_15") (pintype "passive"))
    )
    (net (code "127") (name "GND") (class "Default")
      (node (ref "3.3vto5v") (pin "2") (pinfunction "GND_2") (pintype "passive"))
      (node (ref "4067") (pin "12") (pinfunction "GND_12") (pintype "passive"))
      (node (ref "4067") (pin "15") (pinfunction "~{E}_15") (pintype "passive"))
      (node (ref "ALPS EC1") (pin "C1") (pinfunction "C1_C1") (pintype "passive"))
      (node (ref "ALPS EC1") (pin "W1") (pinfunction "W1_W1") (pintype "passive"))
      (node (ref "ALPS EC10") (pin "C1") (pinfunction "C1_C1") (pintype "passive"))
      (node (ref "ALPS EC10") (pin "W1") (pinfunction "W1_W1") (pintype "passive"))
      (node (ref "ALPS EC11") (pin "C1") (pinfunction "C1_C1") (pintype "passive"))
      (node (ref "ALPS EC11") (pin "W1") (pinfunction "W1_W1") (pintype "passive"))
      (node (ref "ALPS EC12") (pin "C1") (pinfunction "C1_C1") (pintype "passive"))
      (node (ref "ALPS EC12") (pin "W1") (pinfunction "W1_W1") (pintype "passive"))
      (node (ref "ALPS EC13") (pin "C1") (pinfunction "C1_C1") (pintype "passive"))
      (node (ref "ALPS EC13") (pin "W1") (pinfunction "W1_W1") (pintype "passive"))
      (node (ref "ALPS EC14") (pin "C1") (pinfunction "C1_C1") (pintype "passive"))
      (node (ref "ALPS EC14") (pin "W1") (pinfunction "W1_W1") (pintype "passive"))
      (node (ref "ALPS EC15") (pin "C1") (pinfunction "C1_C1") (pintype "passive"))
      (node (ref "ALPS EC15") (pin "W1") (pinfunction "W1_W1") (pintype "passive"))
      (node (ref "ALPS EC16") (pin "C1") (pinfunction "C1_C1") (pintype "passive"))
      (node (ref "ALPS EC16") (pin "W1") (pinfunction "W1_W1") (pintype "passive"))
      (node (ref "ALPS EC2") (pin "C1") (pinfunction "C1_C1") (pintype "passive"))
      (node (ref "ALPS EC2") (pin "W1") (pinfunction "W1_W1") (pintype "passive"))
      (node (ref "ALPS EC3") (pin "C1") (pinfunction "C1_C1") (pintype "passive"))
      (node (ref "ALPS EC3") (pin "W1") (pinfunction "W1_W1") (pintype "passive"))
      (node (ref "ALPS EC4") (pin "C1") (pinfunction "C1_C1") (pintype "passive"))
      (node (ref "ALPS EC4") (pin "W1") (pinfunction "W1_W1") (pintype "passive"))
      (node (ref "ALPS EC5") (pin "C1") (pinfunction "C1_C1") (pintype "passive"))
      (node (ref "ALPS EC5") (pin "W1") (pinfunction "W1_W1") (pintype "passive"))
      (node (ref "ALPS EC6") (pin "C1") (pinfunction "C1_C1") (pintype "passive"))
      (node (ref "ALPS EC6") (pin "W1") (pinfunction "W1_W1") (pintype "passive"))
      (node (ref "ALPS EC7") (pin "C1") (pinfunction "C1_C1") (pintype "passive"))
      (node (ref "ALPS EC7") (pin "W1") (pinfunction "W1_W1") (pintype "passive"))
      (node (ref "ALPS EC8") (pin "C1") (pinfunction "C1_C1") (pintype "passive"))
      (node (ref "ALPS EC8") (pin "W1") (pinfunction "W1_W1") (pintype "passive"))
      (node (ref "ALPS EC9") (pin "C1") (pinfunction "C1_C1") (pintype "passive"))
      (node (ref "ALPS EC9") (pin "W1") (pinfunction "W1_W1") (pintype "passive"))
      (node (ref "C1") (pin "2") (pinfunction "2_2") (pintype "passive"))
      (node (ref "C10") (pin "2") (pinfunction "2_2") (pintype "passive"))
      (node (ref "C11") (pin "1") (pinfunction "1_1") (pintype "passive"))
      (node (ref "C2") (pin "1") (pinfunction "1_1") (pintype "passive"))
      (node (ref "C3") (pin "2") (pinfunction "2_2") (pintype "passive"))
      (node (ref "C4") (pin "1") (pinfunction "1_1") (pintype "passive"))
      (node (ref "C5") (pin "2") (pinfunction "2_2") (pintype "passive"))
      (node (ref "C6") (pin "1") (pinfunction "1_1") (pintype "passive"))
      (node (ref "C7") (pin "2") (pinfunction "2_2") (pintype "passive"))
      (node (ref "C8") (pin "1") (pinfunction "1_1") (pintype "passive"))
      (node (ref "C9") (pin "1") (pinfunction "1_1") (pintype "passive"))
      (node (ref "ec11page") (pin "C1") (pinfunction "C1_C1") (pintype "passive"))
      (node (ref "ec11page") (pin "W1") (pinfunction "W1_W1") (pintype "passive"))
      (node (ref "esp32S2") (pin "GND") (pinfunction "GND_GND") (pintype "passive"))
      (node (ref "esp32S3") (pin "1") (pinfunction "GND_1") (pintype "passive"))
      (node (ref "esp32S3") (pin "22") (pinfunction "gnd_3_22") (pintype "passive"))
      (node (ref "max1") (pin "4") (pinfunction "GND_1_4") (pintype "passive"))
      (node (ref "max1") (pin "9") (pinfunction "GND_2_9") (pintype "passive"))
      (node (ref "max2") (pin "4") (pinfunction "GND_1_4") (pintype "passive"))
      (node (ref "max2") (pin "9") (pinfunction "GND_2_9") (pintype "passive"))
      (node (ref "max3") (pin "4") (pinfunction "GND_1_4") (pintype "passive"))
      (node (ref "max3") (pin "9") (pinfunction "GND_2_9") (pintype "passive"))
      (node (ref "max4") (pin "4") (pinfunction "GND_1_4") (pintype "passive"))
      (node (ref "max4") (pin "9") (pinfunction "GND_2_9") (pintype "passive"))
      (node (ref "mcp1") (pin "10") (pinfunction "VSS_10") (pintype "passive"))
      (node (ref "mcp1") (pin "15") (pinfunction "A0_15") (pintype "passive"))
      (node (ref "mcp1") (pin "16") (pinfunction "A2_1_16") (pintype "passive"))
      (node (ref "mcp1") (pin "17") (pinfunction "A2_2_17") (pintype "passive"))
      (node (ref "mcp2") (pin "10") (pinfunction "VSS_10") (pintype "passive"))
      (node (ref "mcp2") (pin "16") (pinfunction "A2_1_16") (pintype "passive"))
      (node (ref "mcp2") (pin "17") (pinfunction "A2_2_17") (pintype "passive"))
    )
    (net (code "128") (name "Net-(esp32S3-gpio13)") (class "Default")
      (node (ref "10kR1") (pin "2") (pinfunction "2_2") (pintype "passive"))
      (node (ref "ec11page") (pin "B1") (pinfunction "B1_B1") (pintype "passive"))
      (node (ref "esp32S3") (pin "41") (pinfunction "gpio13_41") (pintype "passive"))
    )
    (net (code "129") (name "Net-(esp32S3-gpio14)") (class "Default")
      (node (ref "10kR2") (pin "1") (pinfunction "1_1") (pintype "passive"))
      (node (ref "ec11page") (pin "A1") (pinfunction "A1_A1") (pintype "passive"))
      (node (ref "esp32S3") (pin "40") (pinfunction "gpio14_40") (pintype "passive"))
    )
    (net (code "130") (name "Net-(esp32S3-gpio21)") (class "Default")
      (node (ref "ec11page") (pin "S1") (pinfunction "S1_S1") (pintype "passive"))
      (node (ref "esp32S3") (pin "39") (pinfunction "gpio21_39") (pintype "passive"))
    )
    (net (code "131") (name "Net-(max1-DOUT)") (class "Default")
      (node (ref "max1") (pin "24") (pinfunction "DOUT_24") (pintype "passive"))
      (node (ref "max2") (pin "1") (pinfunction "DIN_1") (pintype "passive"))
    )
    (net (code "132") (name "Net-(max1-ISET)") (class "Default")
      (node (ref "max1") (pin "18") (pinfunction "ISET_18") (pintype "passive"))
      (node (ref "r1") (pin "1") (pinfunction "1_1") (pintype "passive"))
    )
    (net (code "133") (name "Net-(max2-DOUT)") (class "Default")
      (node (ref "max2") (pin "24") (pinfunction "DOUT_24") (pintype "passive"))
      (node (ref "max3") (pin "1") (pinfunction "DIN_1") (pintype "passive"))
    )
    (net (code "134") (name "Net-(max2-ISET)") (class "Default")
      (node (ref "max2") (pin "18") (pinfunction "ISET_18") (pintype "passive"))
      (node (ref "r2") (pin "1") (pinfunction "1_1") (pintype "passive"))
    )
    (net (code "135") (name "Net-(max3-DOUT)") (class "Default")
      (node (ref "max3") (pin "24") (pinfunction "DOUT_24") (pintype "passive"))
      (node (ref "max4") (pin "1") (pinfunction "DIN_1") (pintype "passive"))
    )
    (net (code "136") (name "Net-(max3-ISET)") (class "Default")
      (node (ref "max3") (pin "18") (pinfunction "ISET_18") (pintype "passive"))
      (node (ref "r3") (pin "1") (pinfunction "1_1") (pintype "passive"))
    )
    (net (code "137") (name "Net-(max4-ISET)") (class "Default")
      (node (ref "max4") (pin "18") (pinfunction "ISET_18") (pintype "passive"))
      (node (ref "r4") (pin "1") (pinfunction "1_1") (pintype "passive"))
    )
    (net (code "138") (name "Net-(mcp1-~{RESET})") (class "Default")
      (node (ref "mcp1") (pin "18") (pinfunction "~{RESET}_18") (pintype "passive"))
      (node (ref "rmcp1") (pin "1") (pinfunction "1_1") (pintype "passive"))
    )
    (net (code "139") (name "Net-(mcp2-~{RESET})") (class "Default")
      (node (ref "mcp2") (pin "18") (pinfunction "~{RESET}_18") (pintype "passive"))
      (node (ref "rmcp2") (pin "1") (pinfunction "1_1") (pintype "passive"))
    )
    (net (code "140") (name "unconnected-(ALPS EC1-PadMH1)") (class "Default")
      (node (ref "ALPS EC1") (pin "MH1") (pinfunction "MH1_MH1") (pintype "passive"))
    )
    (net (code "141") (name "unconnected-(ALPS EC1-PadMH2)") (class "Default")
      (node (ref "ALPS EC1") (pin "MH2") (pinfunction "MH2_MH2") (pintype "passive"))
    )
    (net (code "142") (name "unconnected-(ALPS EC2-PadMH1)") (class "Default")
      (node (ref "ALPS EC2") (pin "MH1") (pinfunction "MH1_MH1") (pintype "passive"))
    )
    (net (code "143") (name "unconnected-(ALPS EC2-PadMH2)") (class "Default")
      (node (ref "ALPS EC2") (pin "MH2") (pinfunction "MH2_MH2") (pintype "passive"))
    )
    (net (code "144") (name "unconnected-(ALPS EC3-PadMH1)") (class "Default")
      (node (ref "ALPS EC3") (pin "MH1") (pinfunction "MH1_MH1") (pintype "passive"))
    )
    (net (code "145") (name "unconnected-(ALPS EC3-PadMH2)") (class "Default")
      (node (ref "ALPS EC3") (pin "MH2") (pinfunction "MH2_MH2") (pintype "passive"))
    )
    (net (code "146") (name "unconnected-(ALPS EC4-PadMH1)") (class "Default")
      (node (ref "ALPS EC4") (pin "MH1") (pinfunction "MH1_MH1") (pintype "passive"))
    )
    (net (code "147") (name "unconnected-(ALPS EC4-PadMH2)") (class "Default")
      (node (ref "ALPS EC4") (pin "MH2") (pinfunction "MH2_MH2") (pintype "passive"))
    )
    (net (code "148") (name "unconnected-(ALPS EC5-PadMH1)") (class "Default")
      (node (ref "ALPS EC5") (pin "MH1") (pinfunction "MH1_MH1") (pintype "passive"))
    )
    (net (code "149") (name "unconnected-(ALPS EC5-PadMH2)") (class "Default")
      (node (ref "ALPS EC5") (pin "MH2") (pinfunction "MH2_MH2") (pintype "passive"))
    )
    (net (code "150") (name "unconnected-(ALPS EC6-PadMH1)") (class "Default")
      (node (ref "ALPS EC6") (pin "MH1") (pinfunction "MH1_MH1") (pintype "passive"))
    )
    (net (code "151") (name "unconnected-(ALPS EC6-PadMH2)") (class "Default")
      (node (ref "ALPS EC6") (pin "MH2") (pinfunction "MH2_MH2") (pintype "passive"))
    )
    (net (code "152") (name "unconnected-(ALPS EC7-PadMH1)") (class "Default")
      (node (ref "ALPS EC7") (pin "MH1") (pinfunction "MH1_MH1") (pintype "passive"))
    )
    (net (code "153") (name "unconnected-(ALPS EC7-PadMH2)") (class "Default")
      (node (ref "ALPS EC7") (pin "MH2") (pinfunction "MH2_MH2") (pintype "passive"))
    )
    (net (code "154") (name "unconnected-(ALPS EC8-PadMH1)") (class "Default")
      (node (ref "ALPS EC8") (pin "MH1") (pinfunction "MH1_MH1") (pintype "passive"))
    )
    (net (code "155") (name "unconnected-(ALPS EC8-PadMH2)") (class "Default")
      (node (ref "ALPS EC8") (pin "MH2") (pinfunction "MH2_MH2") (pintype "passive"))
    )
    (net (code "156") (name "unconnected-(ALPS EC9-PadMH1)") (class "Default")
      (node (ref "ALPS EC9") (pin "MH1") (pinfunction "MH1_MH1") (pintype "passive"))
    )
    (net (code "157") (name "unconnected-(ALPS EC9-PadMH2)") (class "Default")
      (node (ref "ALPS EC9") (pin "MH2") (pinfunction "MH2_MH2") (pintype "passive"))
    )
    (net (code "158") (name "unconnected-(ALPS EC10-PadMH1)") (class "Default")
      (node (ref "ALPS EC10") (pin "MH1") (pinfunction "MH1_MH1") (pintype "passive"))
    )
    (net (code "159") (name "unconnected-(ALPS EC10-PadMH2)") (class "Default")
      (node (ref "ALPS EC10") (pin "MH2") (pinfunction "MH2_MH2") (pintype "passive"))
    )
    (net (code "160") (name "unconnected-(ALPS EC11-PadMH1)") (class "Default")
      (node (ref "ALPS EC11") (pin "MH1") (pinfunction "MH1_MH1") (pintype "passive"))
    )
    (net (code "161") (name "unconnected-(ALPS EC11-PadMH2)") (class "Default")
      (node (ref "ALPS EC11") (pin "MH2") (pinfunction "MH2_MH2") (pintype "passive"))
    )
    (net (code "162") (name "unconnected-(ALPS EC12-PadMH1)") (class "Default")
      (node (ref "ALPS EC12") (pin "MH1") (pinfunction "MH1_MH1") (pintype "passive"))
    )
    (net (code "163") (name "unconnected-(ALPS EC12-PadMH2)") (class "Default")
      (node (ref "ALPS EC12") (pin "MH2") (pinfunction "MH2_MH2") (pintype "passive"))
    )
    (net (code "164") (name "unconnected-(ALPS EC13-PadMH1)") (class "Default")
      (node (ref "ALPS EC13") (pin "MH1") (pinfunction "MH1_MH1") (pintype "passive"))
    )
    (net (code "165") (name "unconnected-(ALPS EC13-PadMH2)") (class "Default")
      (node (ref "ALPS EC13") (pin "MH2") (pinfunction "MH2_MH2") (pintype "passive"))
    )
    (net (code "166") (name "unconnected-(ALPS EC14-PadMH1)") (class "Default")
      (node (ref "ALPS EC14") (pin "MH1") (pinfunction "MH1_MH1") (pintype "passive"))
    )
    (net (code "167") (name "unconnected-(ALPS EC14-PadMH2)") (class "Default")
      (node (ref "ALPS EC14") (pin "MH2") (pinfunction "MH2_MH2") (pintype "passive"))
    )
    (net (code "168") (name "unconnected-(ALPS EC15-PadMH1)") (class "Default")
      (node (ref "ALPS EC15") (pin "MH1") (pinfunction "MH1_MH1") (pintype "passive"))
    )
    (net (code "169") (name "unconnected-(ALPS EC15-PadMH2)") (class "Default")
      (node (ref "ALPS EC15") (pin "MH2") (pinfunction "MH2_MH2") (pintype "passive"))
    )
    (net (code "170") (name "unconnected-(ALPS EC16-PadMH1)") (class "Default")
      (node (ref "ALPS EC16") (pin "MH1") (pinfunction "MH1_MH1") (pintype "passive"))
    )
    (net (code "171") (name "unconnected-(ALPS EC16-PadMH2)") (class "Default")
      (node (ref "ALPS EC16") (pin "MH2") (pinfunction "MH2_MH2") (pintype "passive"))
    )
    (net (code "172") (name "unconnected-(ec11page-PadMH1)") (class "Default")
      (node (ref "ec11page") (pin "MH1") (pinfunction "MH1_MH1") (pintype "passive"))
    )
    (net (code "173") (name "unconnected-(ec11page-PadMH2)") (class "Default")
      (node (ref "ec11page") (pin "MH2") (pinfunction "MH2_MH2") (pintype "passive"))
    )
    (net (code "174") (name "unconnected-(esp32S2-Pad3V3)") (class "Default")
      (node (ref "esp32S2") (pin "3V3") (pinfunction "3V3_3V3") (pintype "passive"))
    )
    (net (code "175") (name "unconnected-(esp32S2-PadD2)") (class "Default")
      (node (ref "esp32S2") (pin "D2") (pinfunction "D2_D2") (pintype "passive"))
    )
    (net (code "176") (name "unconnected-(esp32S2-PadD4)") (class "Default")
      (node (ref "esp32S2") (pin "D4") (pinfunction "D4_D4") (pintype "passive"))
    )
    (net (code "177") (name "unconnected-(esp32S2-PadD5)") (class "Default")
      (node (ref "esp32S2") (pin "D5") (pinfunction "D5_D5") (pintype "passive"))
    )
    (net (code "178") (name "unconnected-(esp32S2-PadD12)") (class "Default")
      (node (ref "esp32S2") (pin "D12") (pinfunction "D12_D12") (pintype "passive"))
    )
    (net (code "179") (name "unconnected-(esp32S2-PadD13)") (class "Default")
      (node (ref "esp32S2") (pin "D13") (pinfunction "D13_D13") (pintype "passive"))
    )
    (net (code "180") (name "unconnected-(esp32S2-PadD14)") (class "Default")
      (node (ref "esp32S2") (pin "D14") (pinfunction "D14_D14") (pintype "passive"))
    )
    (net (code "181") (name "unconnected-(esp32S2-PadD15)") (class "Default")
      (node (ref "esp32S2") (pin "D15") (pinfunction "D15_D15") (pintype "passive"))
    )
    (net (code "182") (name "unconnected-(esp32S2-PadD23)") (class "Default")
      (node (ref "esp32S2") (pin "D23") (pinfunction "D23_D23") (pintype "passive"))
    )
    (net (code "183") (name "unconnected-(esp32S2-PadD25)") (class "Default")
      (node (ref "esp32S2") (pin "D25") (pinfunction "D25_D25") (pintype "passive"))
    )
    (net (code "184") (name "unconnected-(esp32S2-PadD26)") (class "Default")
      (node (ref "esp32S2") (pin "D26") (pinfunction "D26_D26") (pintype "passive"))
    )
    (net (code "185") (name "unconnected-(esp32S2-PadD27)") (class "Default")
      (node (ref "esp32S2") (pin "D27") (pinfunction "D27_D27") (pintype "passive"))
    )
    (net (code "186") (name "unconnected-(esp32S2-PadD32)") (class "Default")
      (node (ref "esp32S2") (pin "D32") (pinfunction "D32_D32") (pintype "passive"))
    )
    (net (code "187") (name "unconnected-(esp32S2-PadD33)") (class "Default")
      (node (ref "esp32S2") (pin "D33") (pinfunction "D33_D33") (pintype "passive"))
    )
    (net (code "188") (name "unconnected-(esp32S2-PadD34)") (class "Default")
      (node (ref "esp32S2") (pin "D34") (pinfunction "D34_D34") (pintype "passive"))
    )
    (net (code "189") (name "unconnected-(esp32S2-PadD35)") (class "Default")
      (node (ref "esp32S2") (pin "D35") (pinfunction "D35_D35") (pintype "passive"))
    )
    (net (code "190") (name "unconnected-(esp32S2-PadEN)") (class "Default")
      (node (ref "esp32S2") (pin "EN") (pinfunction "EN_EN") (pintype "passive"))
    )
    (net (code "191") (name "unconnected-(esp32S2-PadGND2)") (class "Default")
      (node (ref "esp32S2") (pin "GND2") (pinfunction "GND2_GND2") (pintype "passive"))
    )
    (net (code "192") (name "unconnected-(esp32S2-PadRX0)") (class "Default")
      (node (ref "esp32S2") (pin "RX0") (pinfunction "RX0_RX0") (pintype "passive"))
    )
    (net (code "193") (name "unconnected-(esp32S2-PadRX2)") (class "Default")
      (node (ref "esp32S2") (pin "RX2") (pinfunction "RX2_RX2") (pintype "passive"))
    )
    (net (code "194") (name "unconnected-(esp32S2-PadTX0)") (class "Default")
      (node (ref "esp32S2") (pin "TX0") (pinfunction "TX0_TX0") (pintype "passive"))
    )
    (net (code "195") (name "unconnected-(esp32S2-PadTX2)") (class "Default")
      (node (ref "esp32S2") (pin "TX2") (pinfunction "TX2_TX2") (pintype "passive"))
    )
    (net (code "196") (name "unconnected-(esp32S2-PadVN)") (class "Default")
      (node (ref "esp32S2") (pin "VN") (pinfunction "VN_VN") (pintype "passive"))
    )
    (net (code "197") (name "unconnected-(esp32S2-PadVP)") (class "Default")
      (node (ref "esp32S2") (pin "VP") (pinfunction "VP_VP") (pintype "passive"))
    )
    (net (code "198") (name "unconnected-(esp32S3-3v3-Pad2)") (class "Default")
      (node (ref "esp32S3") (pin "2") (pinfunction "3v3_2") (pintype "passive"))
    )
    (net (code "199") (name "unconnected-(esp32S3-5VVIN-Pad42)") (class "Default")
      (node (ref "esp32S3") (pin "42") (pinfunction "5VVIN_42") (pintype "passive"))
    )
    (net (code "200") (name "unconnected-(esp32S3-RST-Pad3)") (class "Default")
      (node (ref "esp32S3") (pin "3") (pinfunction "RST_3") (pintype "passive"))
    )
    (net (code "201") (name "unconnected-(esp32S3-RXD-Pad26)") (class "Default")
      (node (ref "esp32S3") (pin "26") (pinfunction "RXD_26") (pintype "passive"))
    )
    (net (code "202") (name "unconnected-(esp32S3-TXD-Pad25)") (class "Default")
      (node (ref "esp32S3") (pin "25") (pinfunction "TXD_25") (pintype "passive"))
    )
    (net (code "203") (name "unconnected-(esp32S3-gpio0-Pad35)") (class "Default")
      (node (ref "esp32S3") (pin "35") (pinfunction "gpio0_35") (pintype "passive"))
    )
    (net (code "204") (name "unconnected-(esp32S3-gpio4-Pad4)") (class "Default")
      (node (ref "esp32S3") (pin "4") (pinfunction "gpio4_4") (pintype "passive"))
    )
    (net (code "205") (name "unconnected-(esp32S3-gpio5-Pad5)") (class "Default")
      (node (ref "esp32S3") (pin "5") (pinfunction "gpio5_5") (pintype "passive"))
    )
    (net (code "206") (name "unconnected-(esp32S3-gpio6-Pad6)") (class "Default")
      (node (ref "esp32S3") (pin "6") (pinfunction "gpio6_6") (pintype "passive"))
    )
    (net (code "207") (name "unconnected-(esp32S3-gpio7-Pad7)") (class "Default")
      (node (ref "esp32S3") (pin "7") (pinfunction "gpio7_7") (pintype "passive"))
    )
    (net (code "208") (name "unconnected-(esp32S3-gpio9-Pad17)") (class "Default")
      (node (ref "esp32S3") (pin "17") (pinfunction "gpio9_17") (pintype "passive"))
    )
    (net (code "209") (name "unconnected-(esp32S3-gpio10-Pad18)") (class "Default")
      (node (ref "esp32S3") (pin "18") (pinfunction "gpio10_18") (pintype "passive"))
    )
    (net (code "210") (name "unconnected-(esp32S3-gpio11-Pad19)") (class "Default")
      (node (ref "esp32S3") (pin "19") (pinfunction "gpio11_19") (pintype "passive"))
    )
    (net (code "211") (name "unconnected-(esp32S3-gpio12-Pad20)") (class "Default")
      (node (ref "esp32S3") (pin "20") (pinfunction "gpio12_20") (pintype "passive"))
    )
    (net (code "212") (name "unconnected-(esp32S3-gpio19-Pad13)") (class "Default")
      (node (ref "esp32S3") (pin "13") (pinfunction "gpio19_13") (pintype "passive"))
    )
    (net (code "213") (name "unconnected-(esp32S3-gpio20-Pad14)") (class "Default")
      (node (ref "esp32S3") (pin "14") (pinfunction "gpio20_14") (pintype "passive"))
    )
    (net (code "214") (name "unconnected-(esp32S3-gpio37-Pad32)") (class "Default")
      (node (ref "esp32S3") (pin "32") (pinfunction "gpio37_32") (pintype "passive"))
    )
    (net (code "215") (name "unconnected-(esp32S3-gpio40-Pad29)") (class "Default")
      (node (ref "esp32S3") (pin "29") (pinfunction "gpio40_29") (pintype "passive"))
    )
    (net (code "216") (name "unconnected-(esp32S3-gpio41-Pad28)") (class "Default")
      (node (ref "esp32S3") (pin "28") (pinfunction "gpio41_28") (pintype "passive"))
    )
    (net (code "217") (name "unconnected-(esp32S3-gpio42-Pad27)") (class "Default")
      (node (ref "esp32S3") (pin "27") (pinfunction "gpio42_27") (pintype "passive"))
    )
    (net (code "218") (name "unconnected-(esp32S3-gpio45-Pad36)") (class "Default")
      (node (ref "esp32S3") (pin "36") (pinfunction "gpio45_36") (pintype "passive"))
    )
    (net (code "219") (name "unconnected-(esp32S3-gpio46-Pad16)") (class "Default")
      (node (ref "esp32S3") (pin "16") (pinfunction "gpio46_16") (pintype "passive"))
    )
    (net (code "220") (name "unconnected-(esp32S3-gpio47-Pad38)") (class "Default")
      (node (ref "esp32S3") (pin "38") (pinfunction "gpio47_38") (pintype "passive"))
    )
    (net (code "221") (name "unconnected-(esp32S3-gpio48-Pad37)") (class "Default")
      (node (ref "esp32S3") (pin "37") (pinfunction "gpio48_37") (pintype "passive"))
    )
    (net (code "222") (name "unconnected-(esp32S3-io1-Pad23)") (class "Default")
      (node (ref "esp32S3") (pin "23") (pinfunction "io1_23") (pintype "passive"))
    )
    (net (code "223") (name "unconnected-(esp32S3-io2-Pad24)") (class "Default")
      (node (ref "esp32S3") (pin "24") (pinfunction "io2_24") (pintype "passive"))
    )
    (net (code "224") (name "unconnected-(max4-DOUT-Pad24)") (class "Default")
      (node (ref "max4") (pin "24") (pinfunction "DOUT_24") (pintype "passive"))
    )
    (net (code "225") (name "unconnected-(mcp1-INTA-Pad20)") (class "Default")
      (node (ref "mcp1") (pin "20") (pinfunction "INTA_20") (pintype "passive"))
    )
    (net (code "226") (name "unconnected-(mcp1-INTB-Pad19)") (class "Default")
      (node (ref "mcp1") (pin "19") (pinfunction "INTB_19") (pintype "passive"))
    )
    (net (code "227") (name "unconnected-(mcp1-NC_1-Pad11)") (class "Default")
      (node (ref "mcp1") (pin "11") (pinfunction "NC_1_11") (pintype "passive"))
    )
    (net (code "228") (name "unconnected-(mcp1-NC_2-Pad14)") (class "Default")
      (node (ref "mcp1") (pin "14") (pinfunction "NC_2_14") (pintype "passive"))
    )
    (net (code "229") (name "unconnected-(mcp2-INTA-Pad20)") (class "Default")
      (node (ref "mcp2") (pin "20") (pinfunction "INTA_20") (pintype "passive"))
    )
    (net (code "230") (name "unconnected-(mcp2-INTB-Pad19)") (class "Default")
      (node (ref "mcp2") (pin "19") (pinfunction "INTB_19") (pintype "passive"))
    )
    (net (code "231") (name "unconnected-(mcp2-NC_1-Pad11)") (class "Default")
      (node (ref "mcp2") (pin "11") (pinfunction "NC_1_11") (pintype "passive"))
    )
    (net (code "232") (name "unconnected-(mcp2-NC_2-Pad14)") (class "Default")
      (node (ref "mcp2") (pin "14") (pinfunction "NC_2_14") (pintype "passive"))
    )
  )
)
